# EIT_Recorder.net
KiCad netlist of a schematic drawn in EAGLE
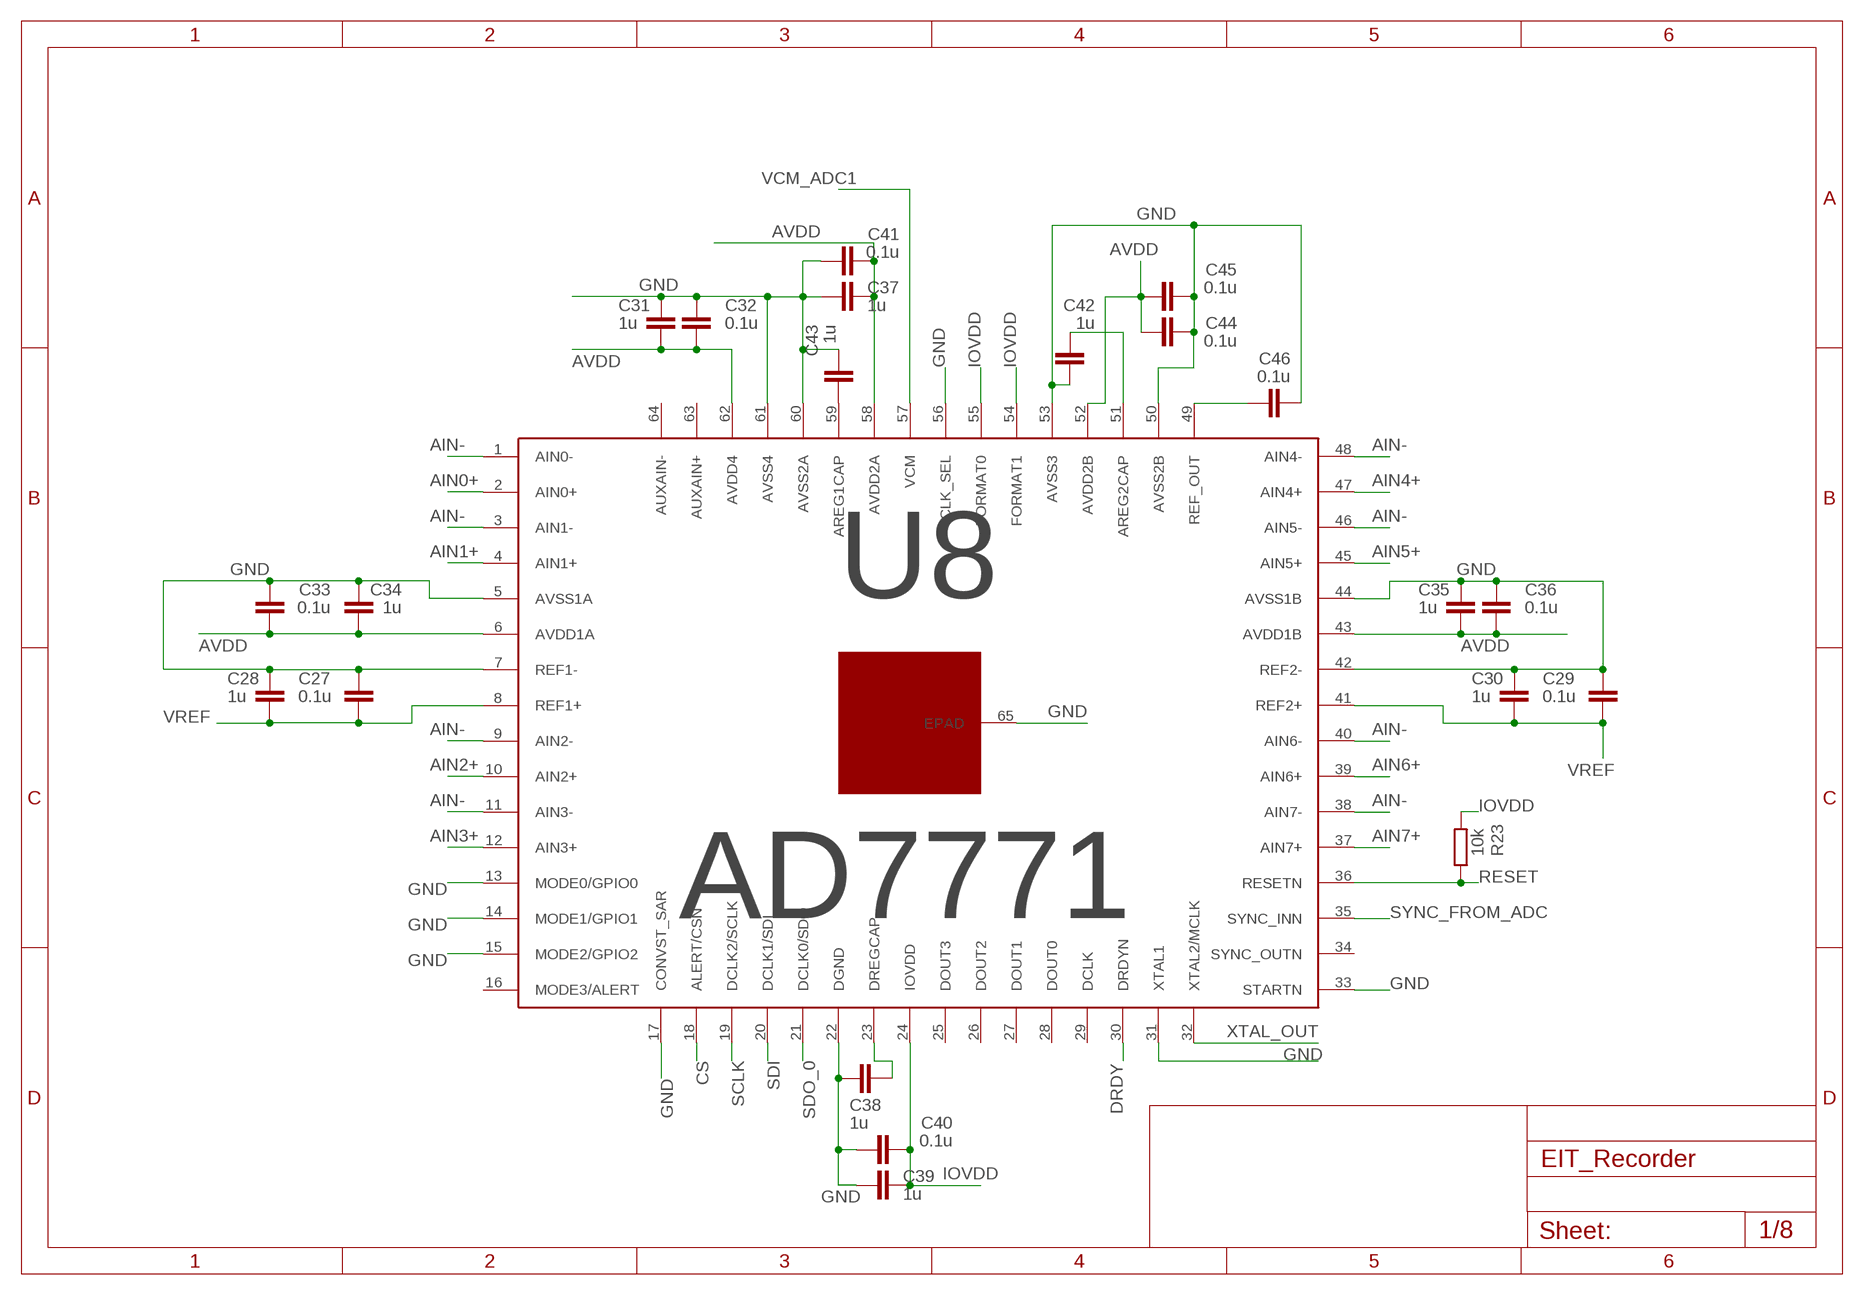
[diagram p0: schematic, sheet 1]
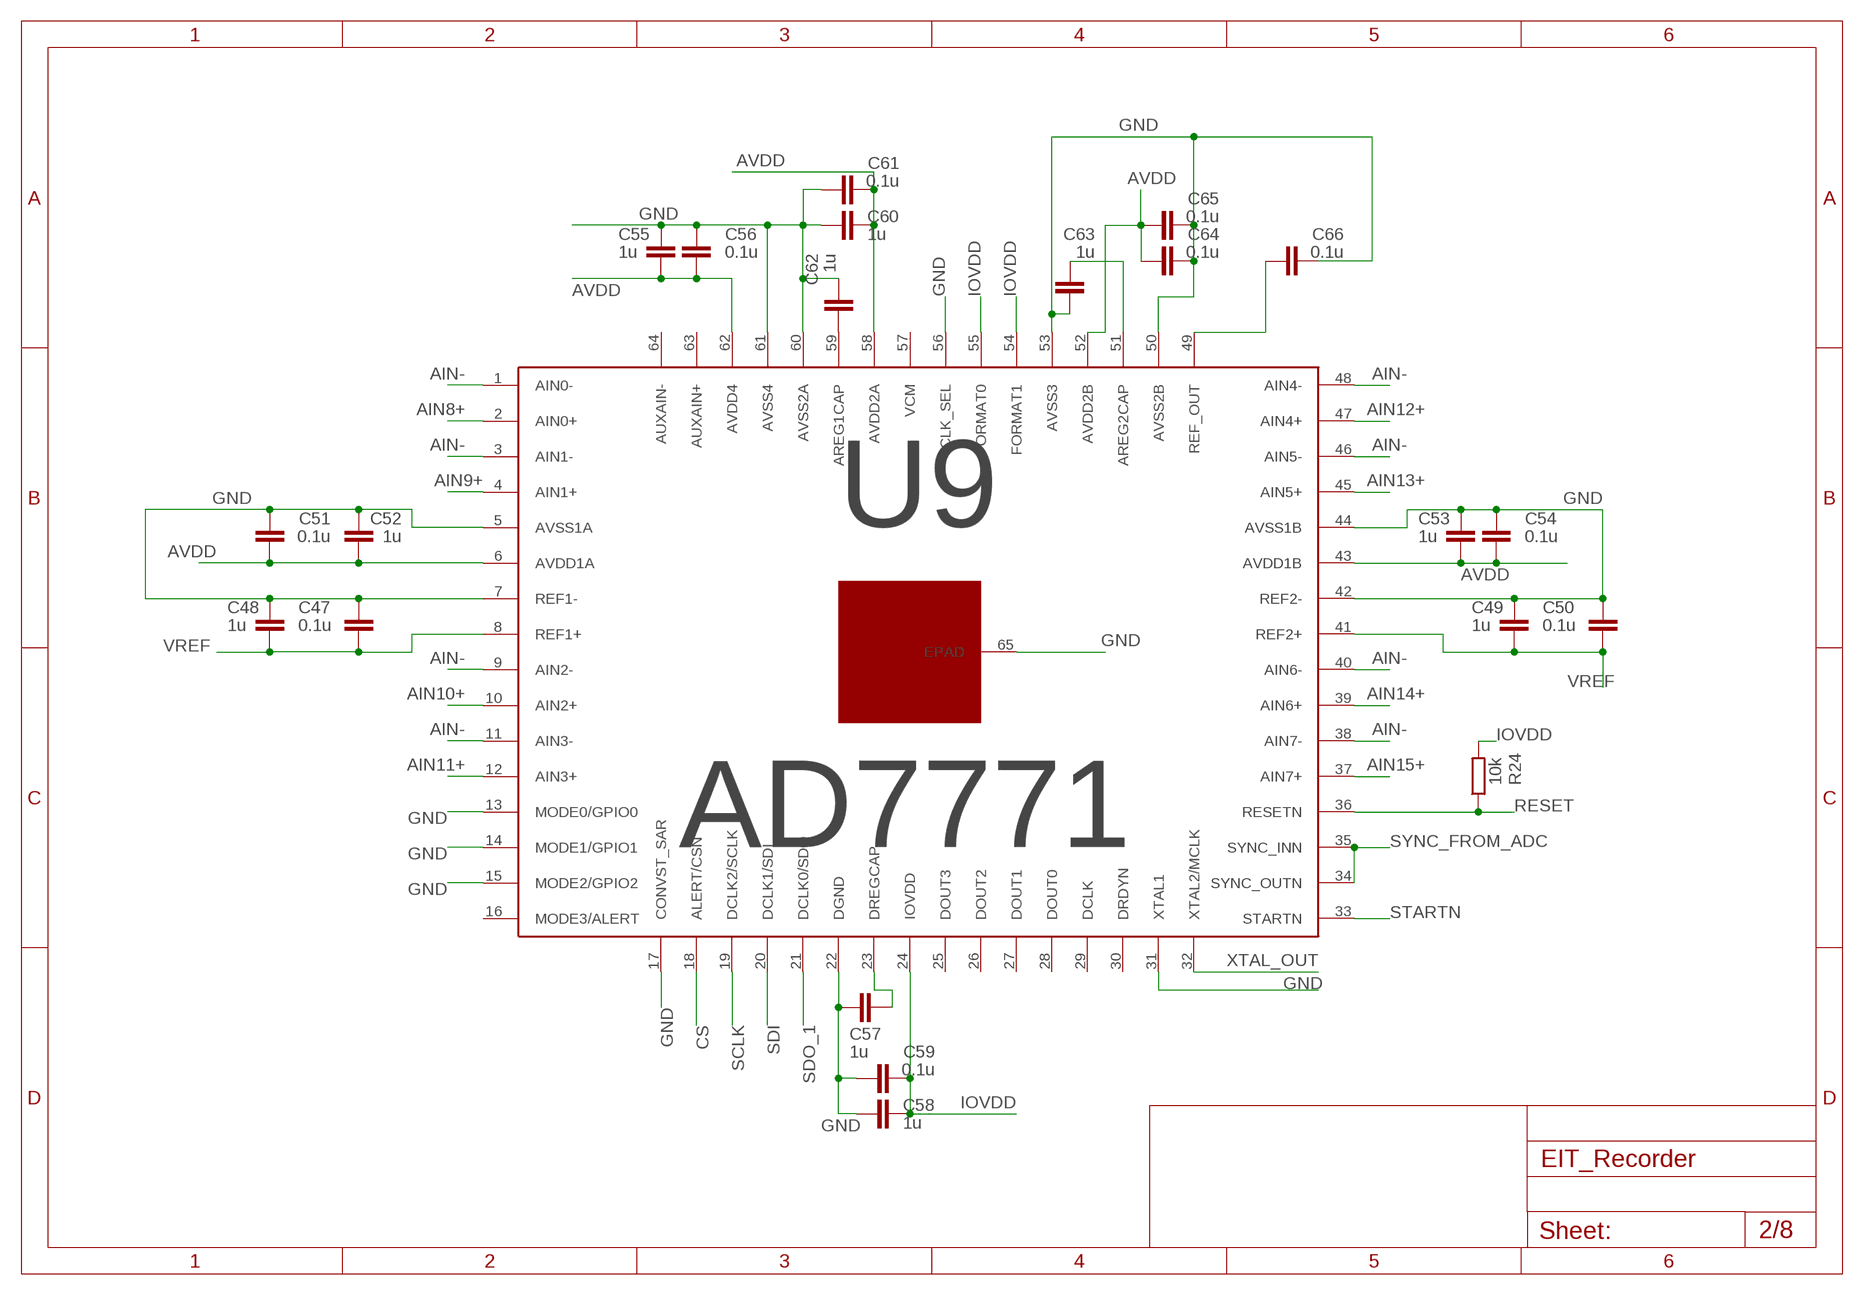
[diagram p1: schematic, sheet 2]
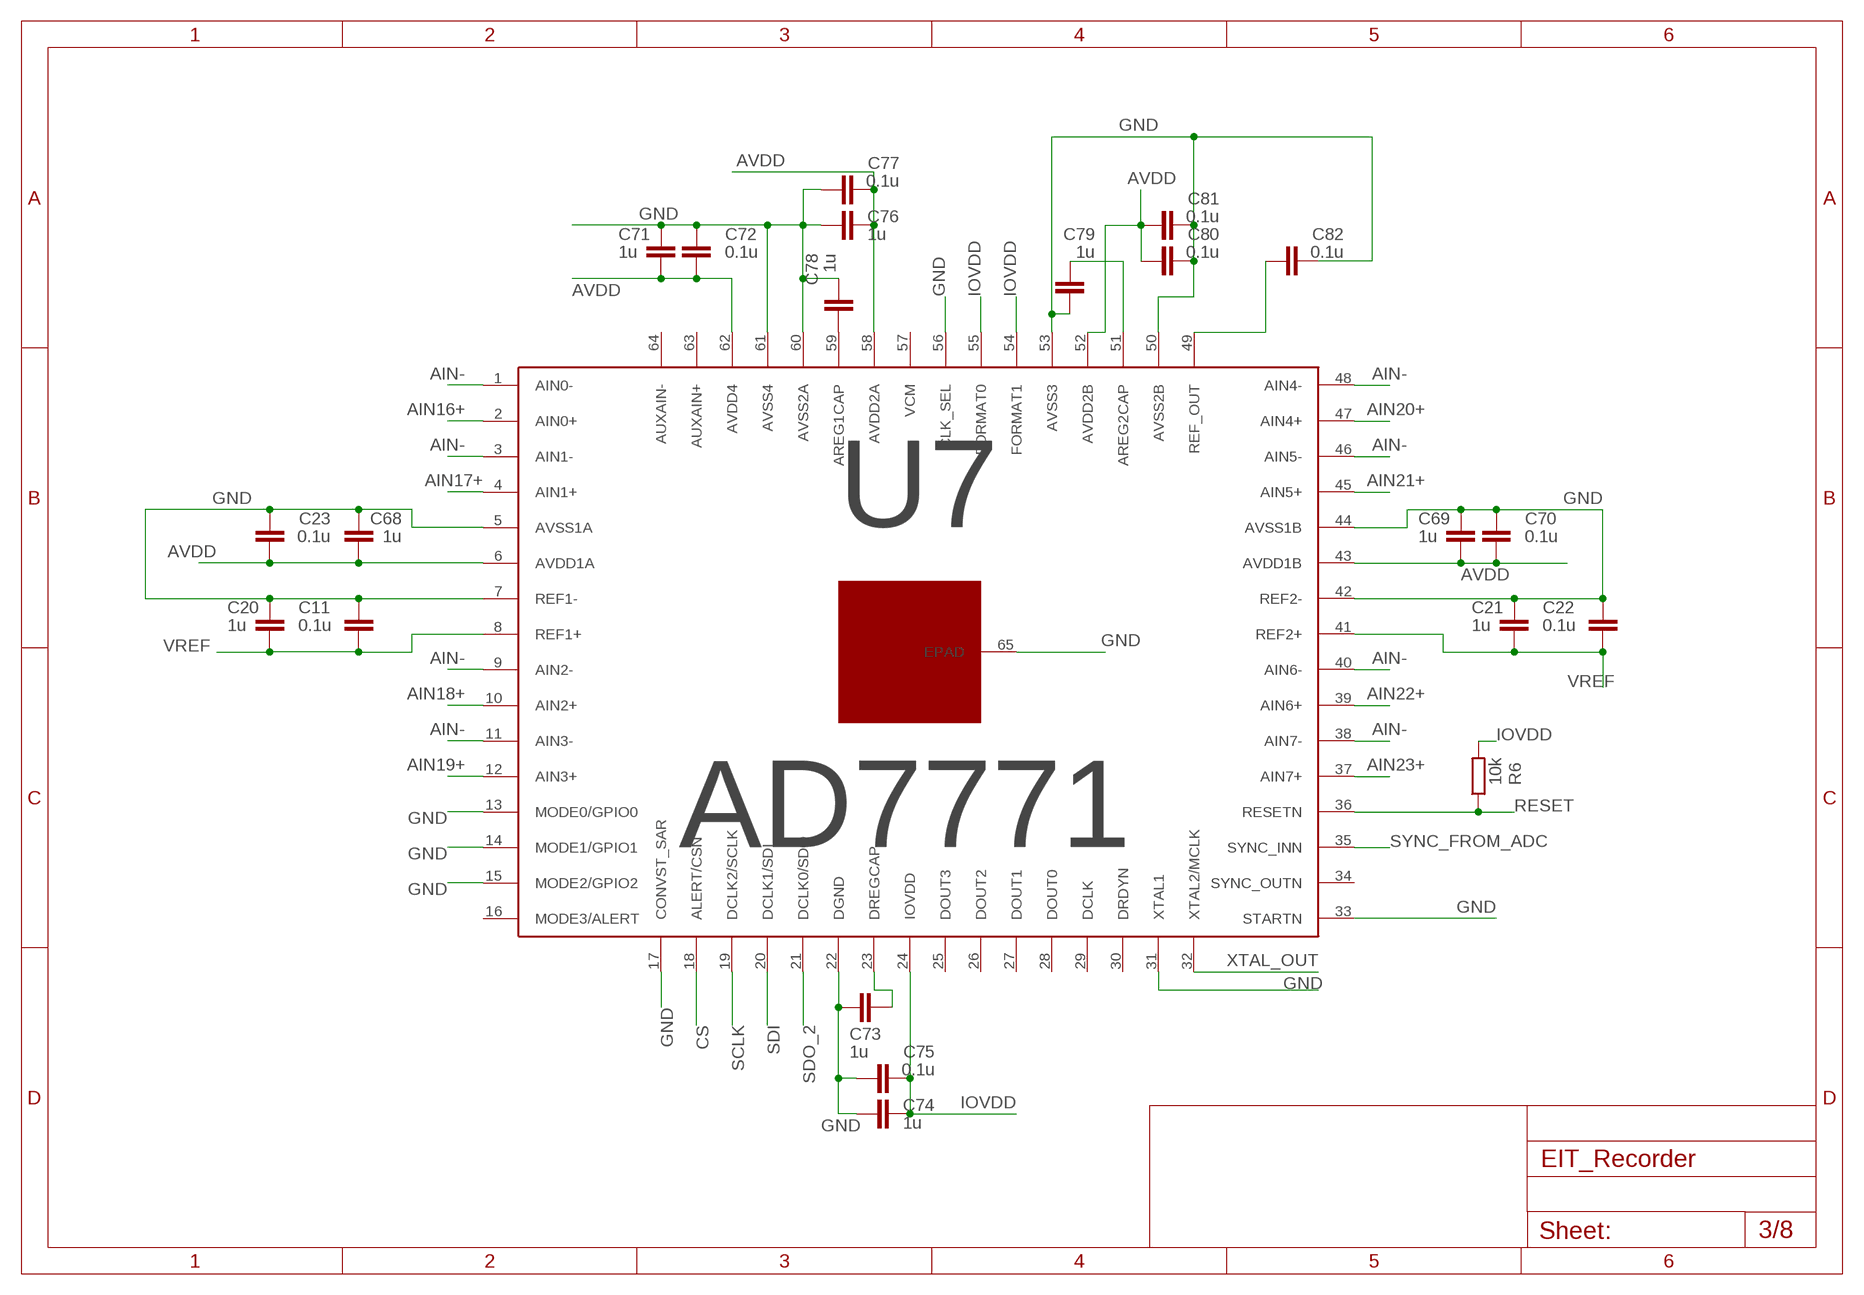
[diagram p2: schematic, sheet 3]
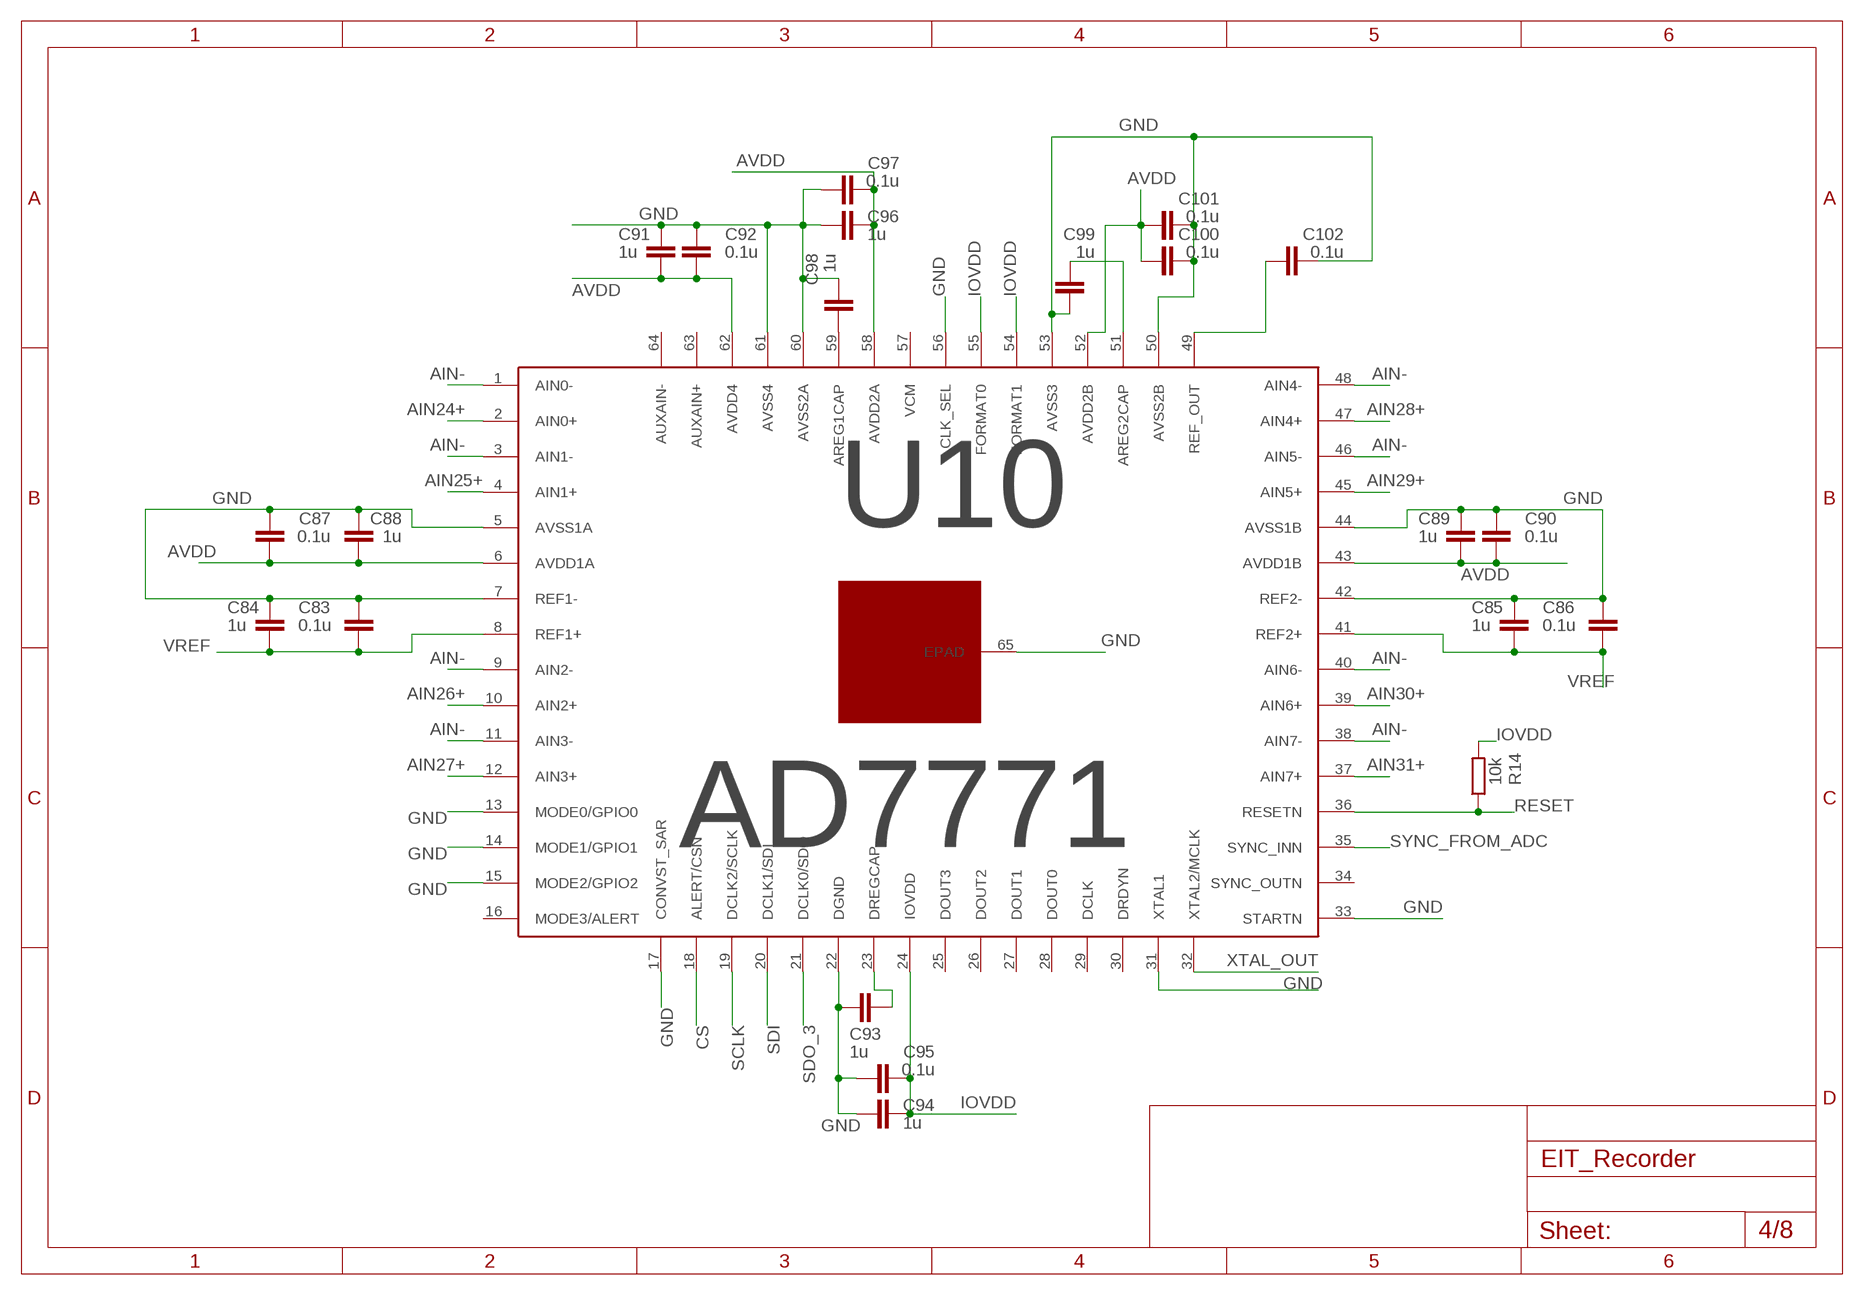
[diagram p3: schematic, sheet 4]
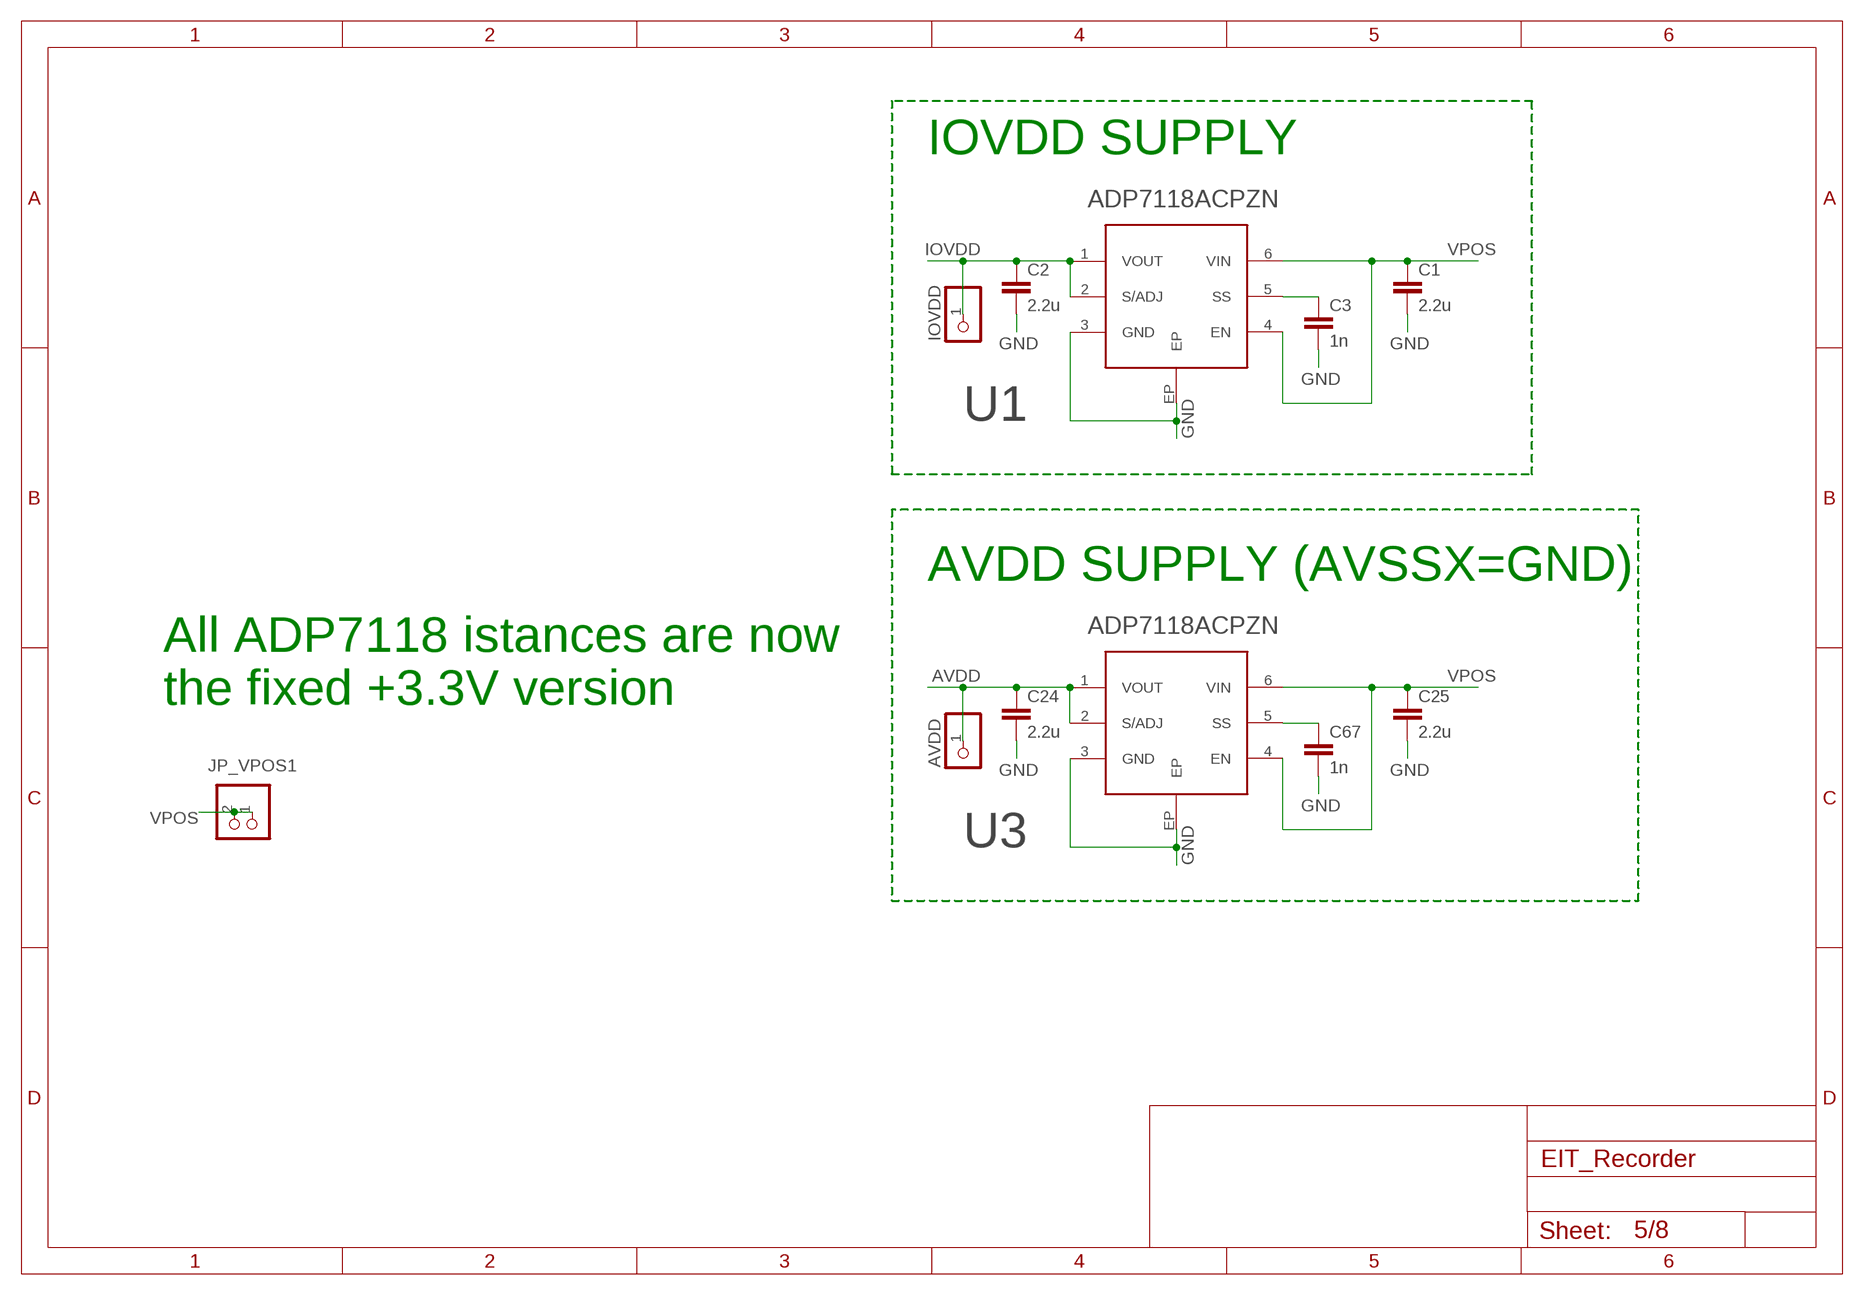
[diagram p4: schematic, sheet 5]
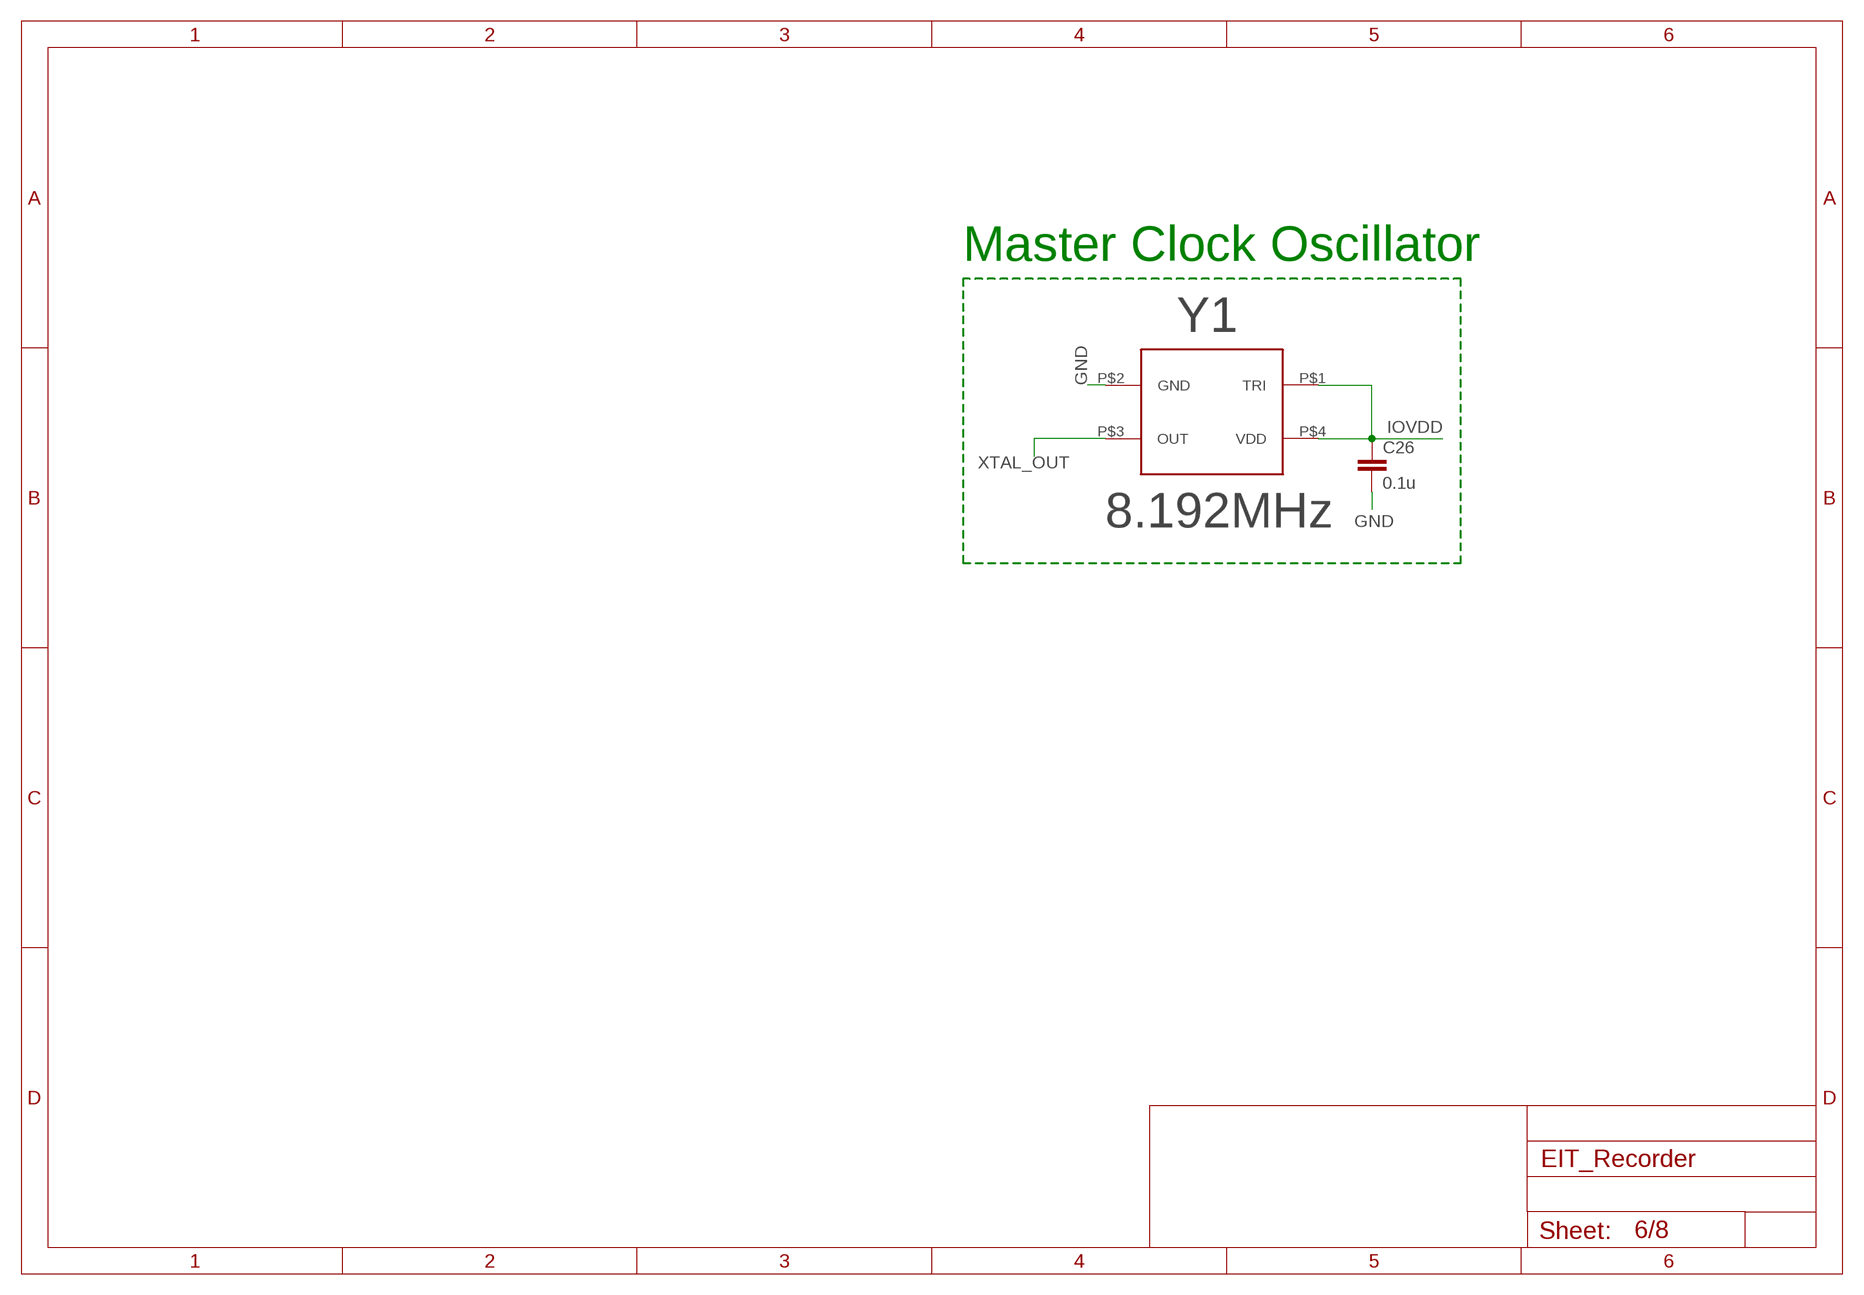
[diagram p5: schematic, sheet 6]
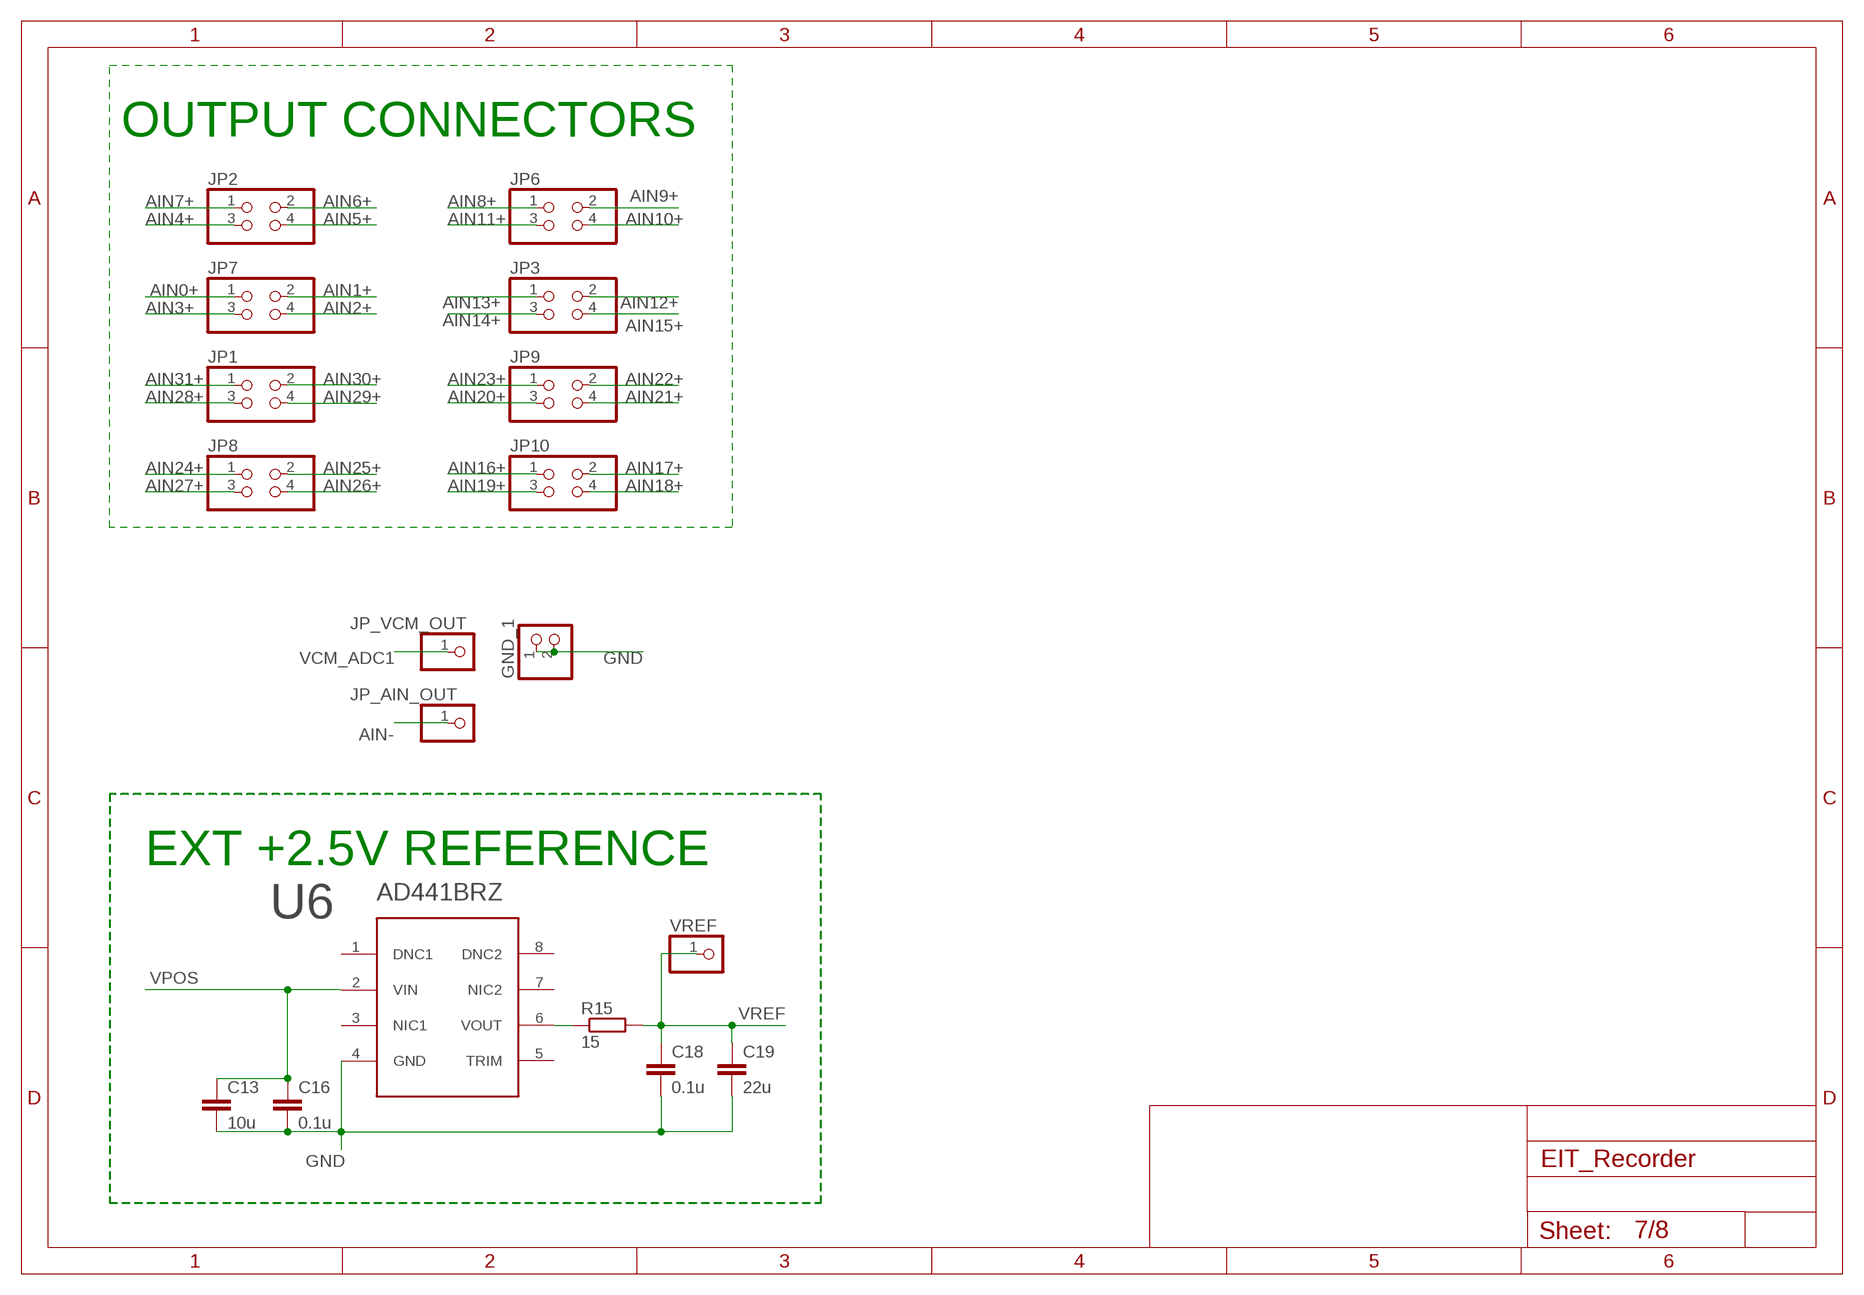
[diagram p6: schematic, sheet 7]
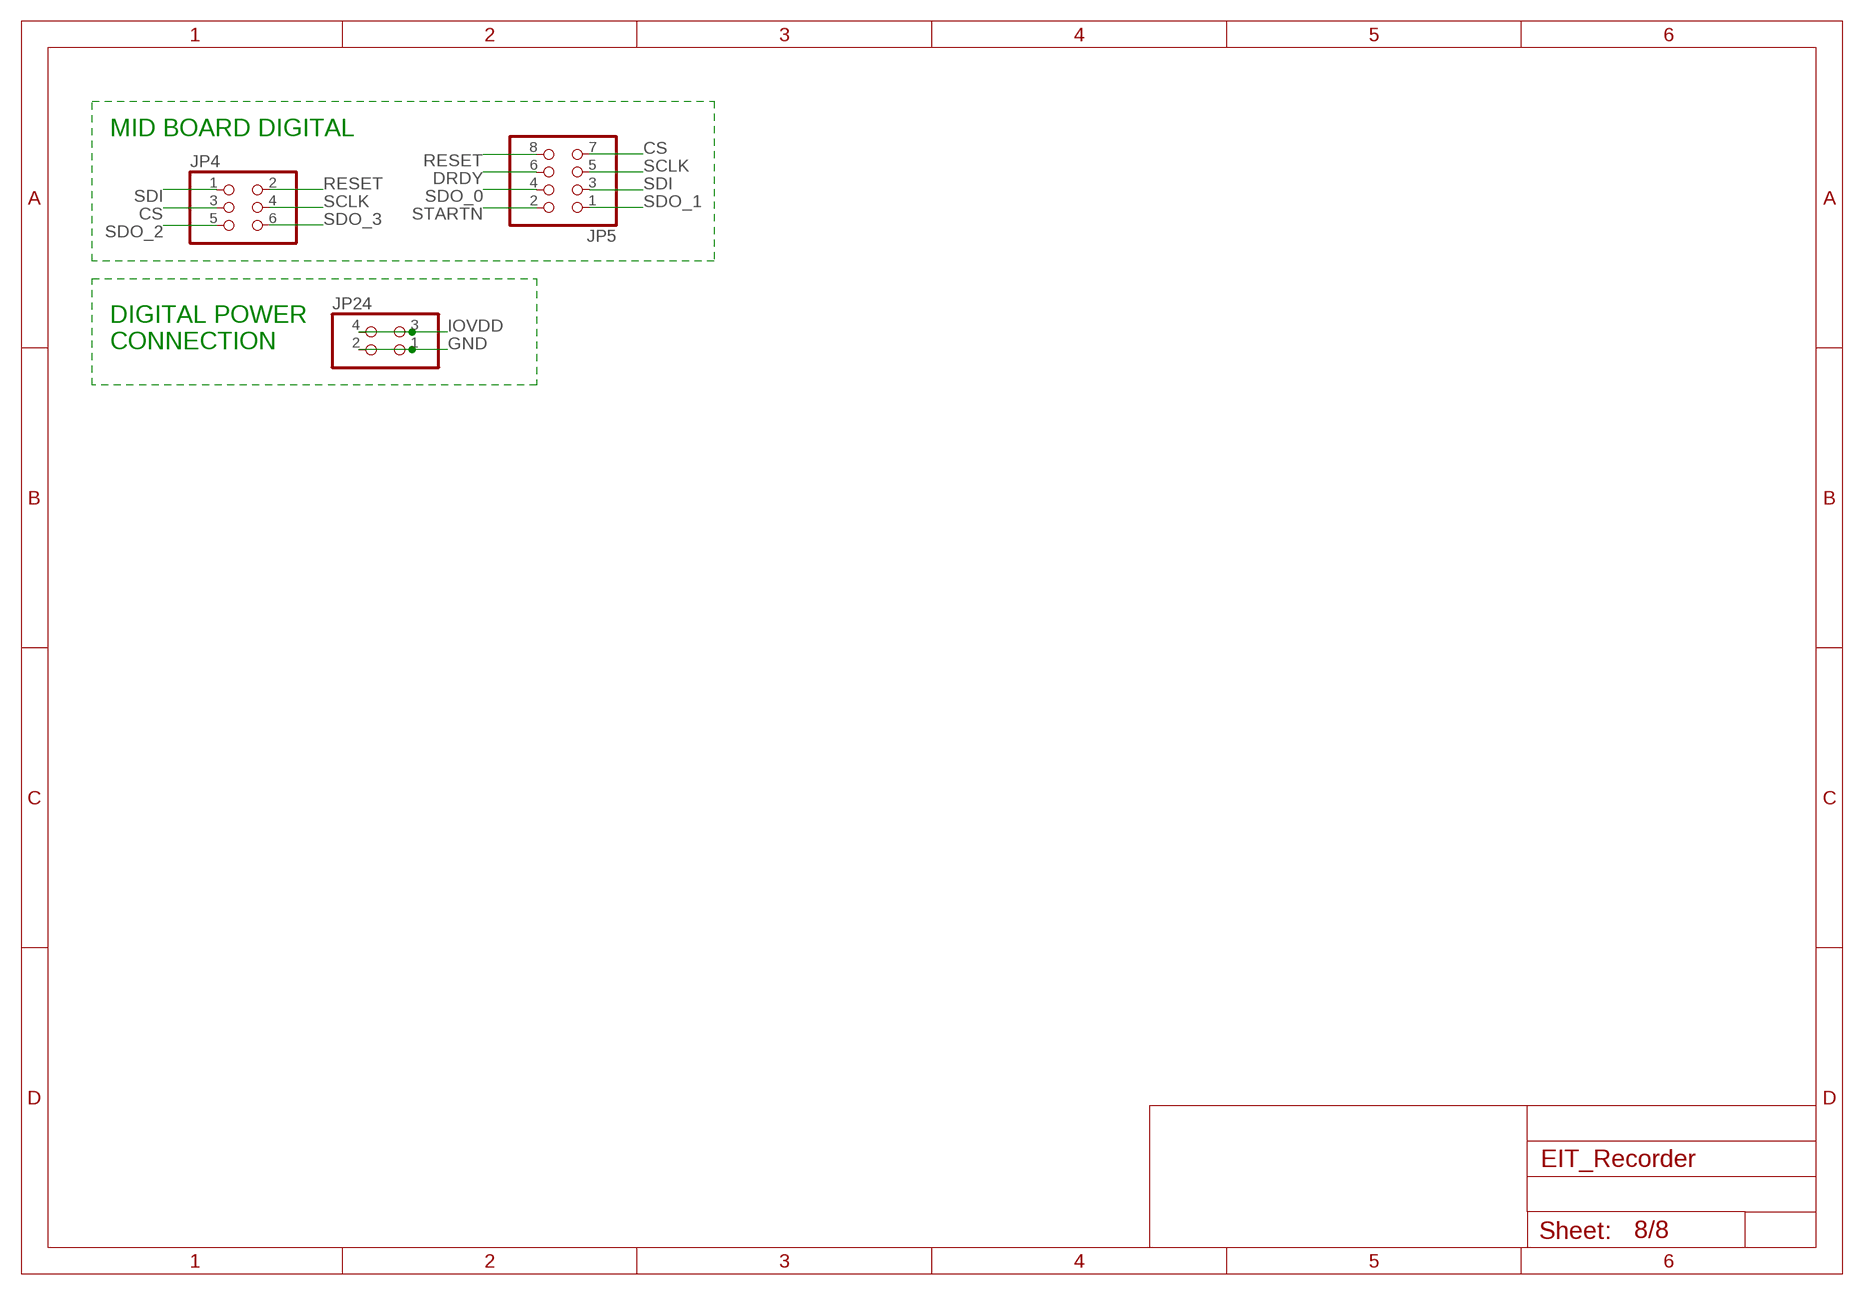
[diagram p7: schematic, sheet 8]

(export (version "E")
  (design (tool "Eeschema 10.0.6"))
  (components
    (comp (ref "C13")
      (value "10u")
      (footprint "eagle-import:C0805")
      (libsource (lib "eagle-import") (part "C0805"))
    )
    (comp (ref "C16")
      (value "0.1u")
      (footprint "eagle-import:C0402")
      (libsource (lib "eagle-import") (part "C0402"))
    )
    (comp (ref "C18")
      (value "0.1u")
      (footprint "eagle-import:C0402")
      (libsource (lib "eagle-import") (part "C0402"))
    )
    (comp (ref "C19")
      (value "22u")
      (footprint "eagle-import:C0805")
      (libsource (lib "eagle-import") (part "C0805"))
    )
    (comp (ref "GND_1")
      (value "PINHD-1X2")
      (footprint "eagle-import:1X02")
      (libsource (lib "eagle-import") (part "PINHD-1X2"))
    )
    (comp (ref "JP1")
      (value "PINHD-2X2")
      (footprint "eagle-import:2X02")
      (libsource (lib "eagle-import") (part "PINHD-2X2"))
    )
    (comp (ref "JP2")
      (value "PINHD-2X2")
      (footprint "eagle-import:2X02")
      (libsource (lib "eagle-import") (part "PINHD-2X2"))
    )
    (comp (ref "JP3")
      (value "PINHD-2X2")
      (footprint "eagle-import:2X02")
      (libsource (lib "eagle-import") (part "PINHD-2X2"))
    )
    (comp (ref "JP6")
      (value "PINHD-2X2")
      (footprint "eagle-import:2X02")
      (libsource (lib "eagle-import") (part "PINHD-2X2"))
    )
    (comp (ref "JP7")
      (value "PINHD-2X2")
      (footprint "eagle-import:2X02")
      (libsource (lib "eagle-import") (part "PINHD-2X2"))
    )
    (comp (ref "JP8")
      (value "PINHD-2X2")
      (footprint "eagle-import:2X02")
      (libsource (lib "eagle-import") (part "PINHD-2X2"))
    )
    (comp (ref "JP9")
      (value "PINHD-2X2")
      (footprint "eagle-import:2X02")
      (libsource (lib "eagle-import") (part "PINHD-2X2"))
    )
    (comp (ref "JP10")
      (value "PINHD-2X2")
      (footprint "eagle-import:2X02")
      (libsource (lib "eagle-import") (part "PINHD-2X2"))
    )
    (comp (ref "JP_AIN_OUT")
      (value "PINHD-1X1")
      (footprint "eagle-import:1X01")
      (libsource (lib "eagle-import") (part "PINHD-1X1"))
    )
    (comp (ref "JP_VCM_OUT")
      (value "PINHD-1X1")
      (footprint "eagle-import:1X01")
      (libsource (lib "eagle-import") (part "PINHD-1X1"))
    )
    (comp (ref "R15")
      (value "15")
      (footprint "eagle-import:R0603")
      (libsource (lib "eagle-import") (part "R0603"))
    )
    (comp (ref "U6")
      (value "AD441BRZ")
      (footprint "eagle-import:SOIC8N_CUSTOM")
      (libsource (lib "eagle-import") (part "AD441BRZ"))
    )
    (comp (ref "VREF")
      (value "PINHD-1X1")
      (footprint "eagle-import:1X01")
      (libsource (lib "eagle-import") (part "PINHD-1X1"))
    )
    (comp (ref "C47")
      (value "0.1u")
      (footprint "eagle-import:C0402")
      (libsource (lib "eagle-import") (part "C0402"))
    )
    (comp (ref "C48")
      (value "1u")
      (footprint "eagle-import:C0402")
      (libsource (lib "eagle-import") (part "C0402"))
    )
    (comp (ref "C49")
      (value "1u")
      (footprint "eagle-import:C0402")
      (libsource (lib "eagle-import") (part "C0402"))
    )
    (comp (ref "C50")
      (value "0.1u")
      (footprint "eagle-import:C0402")
      (libsource (lib "eagle-import") (part "C0402"))
    )
    (comp (ref "C51")
      (value "0.1u")
      (footprint "eagle-import:C0402")
      (libsource (lib "eagle-import") (part "C0402"))
    )
    (comp (ref "C52")
      (value "1u")
      (footprint "eagle-import:C0402")
      (libsource (lib "eagle-import") (part "C0402"))
    )
    (comp (ref "C53")
      (value "1u")
      (footprint "eagle-import:C0402")
      (libsource (lib "eagle-import") (part "C0402"))
    )
    (comp (ref "C54")
      (value "0.1u")
      (footprint "eagle-import:C0402")
      (libsource (lib "eagle-import") (part "C0402"))
    )
    (comp (ref "C55")
      (value "1u")
      (footprint "eagle-import:C0402")
      (libsource (lib "eagle-import") (part "C0402"))
    )
    (comp (ref "C56")
      (value "0.1u")
      (footprint "eagle-import:C0402")
      (libsource (lib "eagle-import") (part "C0402"))
    )
    (comp (ref "C57")
      (value "1u")
      (footprint "eagle-import:C0402")
      (libsource (lib "eagle-import") (part "C0402"))
    )
    (comp (ref "C58")
      (value "1u")
      (footprint "eagle-import:C0402")
      (libsource (lib "eagle-import") (part "C0402"))
    )
    (comp (ref "C59")
      (value "0.1u")
      (footprint "eagle-import:C0402")
      (libsource (lib "eagle-import") (part "C0402"))
    )
    (comp (ref "C60")
      (value "1u")
      (footprint "eagle-import:C0402")
      (libsource (lib "eagle-import") (part "C0402"))
    )
    (comp (ref "C61")
      (value "0.1u")
      (footprint "eagle-import:C0402")
      (libsource (lib "eagle-import") (part "C0402"))
    )
    (comp (ref "C62")
      (value "1u")
      (footprint "eagle-import:C0402")
      (libsource (lib "eagle-import") (part "C0402"))
    )
    (comp (ref "C63")
      (value "1u")
      (footprint "eagle-import:C0402")
      (libsource (lib "eagle-import") (part "C0402"))
    )
    (comp (ref "C64")
      (value "0.1u")
      (footprint "eagle-import:C0402")
      (libsource (lib "eagle-import") (part "C0402"))
    )
    (comp (ref "C65")
      (value "0.1u")
      (footprint "eagle-import:C0402")
      (libsource (lib "eagle-import") (part "C0402"))
    )
    (comp (ref "C66")
      (value "0.1u")
      (footprint "eagle-import:C0402")
      (libsource (lib "eagle-import") (part "C0402"))
    )
    (comp (ref "R24")
      (value "10k")
      (footprint "eagle-import:R0603")
      (libsource (lib "eagle-import") (part "R0603"))
    )
    (comp (ref "U9")
      (value "AD7771")
      (footprint "eagle-import:LFCSP64_CUSTOM")
      (libsource (lib "eagle-import") (part "AD7771"))
    )
    (comp (ref "AVDD")
      (value "PINHD-1X1")
      (footprint "eagle-import:1X01")
      (libsource (lib "eagle-import") (part "PINHD-1X1"))
    )
    (comp (ref "C1")
      (value "2.2u")
      (footprint "eagle-import:C0603")
      (libsource (lib "eagle-import") (part "C0603"))
    )
    (comp (ref "C2")
      (value "2.2u")
      (footprint "eagle-import:C0603")
      (libsource (lib "eagle-import") (part "C0603"))
    )
    (comp (ref "C3")
      (value "1n")
      (footprint "eagle-import:C0402")
      (libsource (lib "eagle-import") (part "C0402"))
    )
    (comp (ref "C24")
      (value "2.2u")
      (footprint "eagle-import:C0603")
      (libsource (lib "eagle-import") (part "C0603"))
    )
    (comp (ref "C25")
      (value "2.2u")
      (footprint "eagle-import:C0603")
      (libsource (lib "eagle-import") (part "C0603"))
    )
    (comp (ref "C67")
      (value "1n")
      (footprint "eagle-import:C0402")
      (libsource (lib "eagle-import") (part "C0402"))
    )
    (comp (ref "IOVDD")
      (value "PINHD-1X1")
      (footprint "eagle-import:1X01")
      (libsource (lib "eagle-import") (part "PINHD-1X1"))
    )
    (comp (ref "JP_VPOS1")
      (value "PINHD-1X2")
      (footprint "eagle-import:1X02")
      (libsource (lib "eagle-import") (part "PINHD-1X2"))
    )
    (comp (ref "U1")
      (value "ADP7118ACPZN")
      (footprint "eagle-import:LFCSP6_CUSTOM")
      (libsource (lib "eagle-import") (part "ADP7118ACPZN"))
    )
    (comp (ref "U3")
      (value "ADP7118ACPZN")
      (footprint "eagle-import:LFCSP6_CUSTOM")
      (libsource (lib "eagle-import") (part "ADP7118ACPZN"))
    )
    (comp (ref "C27")
      (value "0.1u")
      (footprint "eagle-import:C0402")
      (libsource (lib "eagle-import") (part "C0402"))
    )
    (comp (ref "C28")
      (value "1u")
      (footprint "eagle-import:C0402")
      (libsource (lib "eagle-import") (part "C0402"))
    )
    (comp (ref "C29")
      (value "0.1u")
      (footprint "eagle-import:C0402")
      (libsource (lib "eagle-import") (part "C0402"))
    )
    (comp (ref "C30")
      (value "1u")
      (footprint "eagle-import:C0402")
      (libsource (lib "eagle-import") (part "C0402"))
    )
    (comp (ref "C31")
      (value "1u")
      (footprint "eagle-import:C0402")
      (libsource (lib "eagle-import") (part "C0402"))
    )
    (comp (ref "C32")
      (value "0.1u")
      (footprint "eagle-import:C0402")
      (libsource (lib "eagle-import") (part "C0402"))
    )
    (comp (ref "C33")
      (value "0.1u")
      (footprint "eagle-import:C0402")
      (libsource (lib "eagle-import") (part "C0402"))
    )
    (comp (ref "C34")
      (value "1u")
      (footprint "eagle-import:C0402")
      (libsource (lib "eagle-import") (part "C0402"))
    )
    (comp (ref "C35")
      (value "1u")
      (footprint "eagle-import:C0402")
      (libsource (lib "eagle-import") (part "C0402"))
    )
    (comp (ref "C36")
      (value "0.1u")
      (footprint "eagle-import:C0402")
      (libsource (lib "eagle-import") (part "C0402"))
    )
    (comp (ref "C37")
      (value "1u")
      (footprint "eagle-import:C0402")
      (libsource (lib "eagle-import") (part "C0402"))
    )
    (comp (ref "C38")
      (value "1u")
      (footprint "eagle-import:C0402")
      (libsource (lib "eagle-import") (part "C0402"))
    )
    (comp (ref "C39")
      (value "1u")
      (footprint "eagle-import:C0402")
      (libsource (lib "eagle-import") (part "C0402"))
    )
    (comp (ref "C40")
      (value "0.1u")
      (footprint "eagle-import:C0402")
      (libsource (lib "eagle-import") (part "C0402"))
    )
    (comp (ref "C41")
      (value "0.1u")
      (footprint "eagle-import:C0402")
      (libsource (lib "eagle-import") (part "C0402"))
    )
    (comp (ref "C42")
      (value "1u")
      (footprint "eagle-import:C0402")
      (libsource (lib "eagle-import") (part "C0402"))
    )
    (comp (ref "C43")
      (value "1u")
      (footprint "eagle-import:C0402")
      (libsource (lib "eagle-import") (part "C0402"))
    )
    (comp (ref "C44")
      (value "0.1u")
      (footprint "eagle-import:C0402")
      (libsource (lib "eagle-import") (part "C0402"))
    )
    (comp (ref "C45")
      (value "0.1u")
      (footprint "eagle-import:C0402")
      (libsource (lib "eagle-import") (part "C0402"))
    )
    (comp (ref "C46")
      (value "0.1u")
      (footprint "eagle-import:C0402")
      (libsource (lib "eagle-import") (part "C0402"))
    )
    (comp (ref "R23")
      (value "10k")
      (footprint "eagle-import:R0603")
      (libsource (lib "eagle-import") (part "R0603"))
    )
    (comp (ref "U8")
      (value "AD7771")
      (footprint "eagle-import:LFCSP64_CUSTOM")
      (libsource (lib "eagle-import") (part "AD7771"))
    )
    (comp (ref "JP4")
      (value "PINHD-2X3")
      (footprint "eagle-import:2X03")
      (libsource (lib "eagle-import") (part "PINHD-2X3"))
    )
    (comp (ref "JP5")
      (value "PINHD-2X4")
      (footprint "eagle-import:2X04")
      (libsource (lib "eagle-import") (part "PINHD-2X4"))
    )
    (comp (ref "JP24")
      (value "PINHD-2X2")
      (footprint "eagle-import:2X02")
      (libsource (lib "eagle-import") (part "PINHD-2X2"))
    )
    (comp (ref "C83")
      (value "0.1u")
      (footprint "eagle-import:C0402")
      (libsource (lib "eagle-import") (part "C0402"))
    )
    (comp (ref "C84")
      (value "1u")
      (footprint "eagle-import:C0402")
      (libsource (lib "eagle-import") (part "C0402"))
    )
    (comp (ref "C85")
      (value "1u")
      (footprint "eagle-import:C0402")
      (libsource (lib "eagle-import") (part "C0402"))
    )
    (comp (ref "C86")
      (value "0.1u")
      (footprint "eagle-import:C0402")
      (libsource (lib "eagle-import") (part "C0402"))
    )
    (comp (ref "C87")
      (value "0.1u")
      (footprint "eagle-import:C0402")
      (libsource (lib "eagle-import") (part "C0402"))
    )
    (comp (ref "C88")
      (value "1u")
      (footprint "eagle-import:C0402")
      (libsource (lib "eagle-import") (part "C0402"))
    )
    (comp (ref "C89")
      (value "1u")
      (footprint "eagle-import:C0402")
      (libsource (lib "eagle-import") (part "C0402"))
    )
    (comp (ref "C90")
      (value "0.1u")
      (footprint "eagle-import:C0402")
      (libsource (lib "eagle-import") (part "C0402"))
    )
    (comp (ref "C91")
      (value "1u")
      (footprint "eagle-import:C0402")
      (libsource (lib "eagle-import") (part "C0402"))
    )
    (comp (ref "C92")
      (value "0.1u")
      (footprint "eagle-import:C0402")
      (libsource (lib "eagle-import") (part "C0402"))
    )
    (comp (ref "C93")
      (value "1u")
      (footprint "eagle-import:C0402")
      (libsource (lib "eagle-import") (part "C0402"))
    )
    (comp (ref "C94")
      (value "1u")
      (footprint "eagle-import:C0402")
      (libsource (lib "eagle-import") (part "C0402"))
    )
    (comp (ref "C95")
      (value "0.1u")
      (footprint "eagle-import:C0402")
      (libsource (lib "eagle-import") (part "C0402"))
    )
    (comp (ref "C96")
      (value "1u")
      (footprint "eagle-import:C0402")
      (libsource (lib "eagle-import") (part "C0402"))
    )
    (comp (ref "C97")
      (value "0.1u")
      (footprint "eagle-import:C0402")
      (libsource (lib "eagle-import") (part "C0402"))
    )
    (comp (ref "C98")
      (value "1u")
      (footprint "eagle-import:C0402")
      (libsource (lib "eagle-import") (part "C0402"))
    )
    (comp (ref "C99")
      (value "1u")
      (footprint "eagle-import:C0402")
      (libsource (lib "eagle-import") (part "C0402"))
    )
    (comp (ref "C100")
      (value "0.1u")
      (footprint "eagle-import:C0402")
      (libsource (lib "eagle-import") (part "C0402"))
    )
    (comp (ref "C101")
      (value "0.1u")
      (footprint "eagle-import:C0402")
      (libsource (lib "eagle-import") (part "C0402"))
    )
    (comp (ref "C102")
      (value "0.1u")
      (footprint "eagle-import:C0402")
      (libsource (lib "eagle-import") (part "C0402"))
    )
    (comp (ref "R14")
      (value "10k")
      (footprint "eagle-import:R0603")
      (libsource (lib "eagle-import") (part "R0603"))
    )
    (comp (ref "U10")
      (value "AD7771")
      (footprint "eagle-import:LFCSP64_CUSTOM")
      (libsource (lib "eagle-import") (part "AD7771"))
    )
    (comp (ref "C26")
      (value "0.1u")
      (footprint "eagle-import:C0402")
      (libsource (lib "eagle-import") (part "C0402"))
    )
    (comp (ref "Y1")
      (value "8.192MHz")
      (footprint "eagle-import:ECS-2520MVLC")
      (libsource (lib "eagle-import") (part "OSC-ECS-2520MVLC"))
    )
    (comp (ref "C11")
      (value "0.1u")
      (footprint "eagle-import:C0402")
      (libsource (lib "eagle-import") (part "C0402"))
    )
    (comp (ref "C20")
      (value "1u")
      (footprint "eagle-import:C0402")
      (libsource (lib "eagle-import") (part "C0402"))
    )
    (comp (ref "C21")
      (value "1u")
      (footprint "eagle-import:C0402")
      (libsource (lib "eagle-import") (part "C0402"))
    )
    (comp (ref "C22")
      (value "0.1u")
      (footprint "eagle-import:C0402")
      (libsource (lib "eagle-import") (part "C0402"))
    )
    (comp (ref "C23")
      (value "0.1u")
      (footprint "eagle-import:C0402")
      (libsource (lib "eagle-import") (part "C0402"))
    )
    (comp (ref "C68")
      (value "1u")
      (footprint "eagle-import:C0402")
      (libsource (lib "eagle-import") (part "C0402"))
    )
    (comp (ref "C69")
      (value "1u")
      (footprint "eagle-import:C0402")
      (libsource (lib "eagle-import") (part "C0402"))
    )
    (comp (ref "C70")
      (value "0.1u")
      (footprint "eagle-import:C0402")
      (libsource (lib "eagle-import") (part "C0402"))
    )
    (comp (ref "C71")
      (value "1u")
      (footprint "eagle-import:C0402")
      (libsource (lib "eagle-import") (part "C0402"))
    )
    (comp (ref "C72")
      (value "0.1u")
      (footprint "eagle-import:C0402")
      (libsource (lib "eagle-import") (part "C0402"))
    )
    (comp (ref "C73")
      (value "1u")
      (footprint "eagle-import:C0402")
      (libsource (lib "eagle-import") (part "C0402"))
    )
    (comp (ref "C74")
      (value "1u")
      (footprint "eagle-import:C0402")
      (libsource (lib "eagle-import") (part "C0402"))
    )
    (comp (ref "C75")
      (value "0.1u")
      (footprint "eagle-import:C0402")
      (libsource (lib "eagle-import") (part "C0402"))
    )
    (comp (ref "C76")
      (value "1u")
      (footprint "eagle-import:C0402")
      (libsource (lib "eagle-import") (part "C0402"))
    )
    (comp (ref "C77")
      (value "0.1u")
      (footprint "eagle-import:C0402")
      (libsource (lib "eagle-import") (part "C0402"))
    )
    (comp (ref "C78")
      (value "1u")
      (footprint "eagle-import:C0402")
      (libsource (lib "eagle-import") (part "C0402"))
    )
    (comp (ref "C79")
      (value "1u")
      (footprint "eagle-import:C0402")
      (libsource (lib "eagle-import") (part "C0402"))
    )
    (comp (ref "C80")
      (value "0.1u")
      (footprint "eagle-import:C0402")
      (libsource (lib "eagle-import") (part "C0402"))
    )
    (comp (ref "C81")
      (value "0.1u")
      (footprint "eagle-import:C0402")
      (libsource (lib "eagle-import") (part "C0402"))
    )
    (comp (ref "C82")
      (value "0.1u")
      (footprint "eagle-import:C0402")
      (libsource (lib "eagle-import") (part "C0402"))
    )
    (comp (ref "R6")
      (value "10k")
      (footprint "eagle-import:R0603")
      (libsource (lib "eagle-import") (part "R0603"))
    )
    (comp (ref "U7")
      (value "AD7771")
      (footprint "eagle-import:LFCSP64_CUSTOM")
      (libsource (lib "eagle-import") (part "AD7771"))
    )
  )
  (nets
    (net (code "1") (name "AIN-") (class "Default")
      (node (ref "JP_AIN_OUT") (pin "1") (pinfunction "1_1") (pintype "passive"))
      (node (ref "U10") (pin "1") (pinfunction "AIN0-_1") (pintype "bidirectional"))
      (node (ref "U10") (pin "11") (pinfunction "AIN3-_11") (pintype "bidirectional"))
      (node (ref "U10") (pin "3") (pinfunction "AIN1-_3") (pintype "bidirectional"))
      (node (ref "U10") (pin "38") (pinfunction "AIN7-_38") (pintype "input"))
      (node (ref "U10") (pin "40") (pinfunction "AIN6-_40") (pintype "input"))
      (node (ref "U10") (pin "46") (pinfunction "AIN5-_46") (pintype "input"))
      (node (ref "U10") (pin "48") (pinfunction "AIN4-_48") (pintype "input"))
      (node (ref "U10") (pin "9") (pinfunction "AIN2-_9") (pintype "bidirectional"))
      (node (ref "U7") (pin "1") (pinfunction "AIN0-_1") (pintype "bidirectional"))
      (node (ref "U7") (pin "11") (pinfunction "AIN3-_11") (pintype "bidirectional"))
      (node (ref "U7") (pin "3") (pinfunction "AIN1-_3") (pintype "bidirectional"))
      (node (ref "U7") (pin "38") (pinfunction "AIN7-_38") (pintype "input"))
      (node (ref "U7") (pin "40") (pinfunction "AIN6-_40") (pintype "input"))
      (node (ref "U7") (pin "46") (pinfunction "AIN5-_46") (pintype "input"))
      (node (ref "U7") (pin "48") (pinfunction "AIN4-_48") (pintype "input"))
      (node (ref "U7") (pin "9") (pinfunction "AIN2-_9") (pintype "bidirectional"))
      (node (ref "U8") (pin "1") (pinfunction "AIN0-_1") (pintype "bidirectional"))
      (node (ref "U8") (pin "11") (pinfunction "AIN3-_11") (pintype "bidirectional"))
      (node (ref "U8") (pin "3") (pinfunction "AIN1-_3") (pintype "bidirectional"))
      (node (ref "U8") (pin "38") (pinfunction "AIN7-_38") (pintype "input"))
      (node (ref "U8") (pin "40") (pinfunction "AIN6-_40") (pintype "input"))
      (node (ref "U8") (pin "46") (pinfunction "AIN5-_46") (pintype "input"))
      (node (ref "U8") (pin "48") (pinfunction "AIN4-_48") (pintype "input"))
      (node (ref "U8") (pin "9") (pinfunction "AIN2-_9") (pintype "bidirectional"))
      (node (ref "U9") (pin "1") (pinfunction "AIN0-_1") (pintype "bidirectional"))
      (node (ref "U9") (pin "11") (pinfunction "AIN3-_11") (pintype "bidirectional"))
      (node (ref "U9") (pin "3") (pinfunction "AIN1-_3") (pintype "bidirectional"))
      (node (ref "U9") (pin "38") (pinfunction "AIN7-_38") (pintype "input"))
      (node (ref "U9") (pin "40") (pinfunction "AIN6-_40") (pintype "input"))
      (node (ref "U9") (pin "46") (pinfunction "AIN5-_46") (pintype "input"))
      (node (ref "U9") (pin "48") (pinfunction "AIN4-_48") (pintype "input"))
      (node (ref "U9") (pin "9") (pinfunction "AIN2-_9") (pintype "bidirectional"))
    )
    (net (code "2") (name "AIN0+") (class "Default")
      (node (ref "JP7") (pin "1") (pinfunction "1_1") (pintype "passive"))
      (node (ref "U8") (pin "2") (pinfunction "AIN0+_2") (pintype "bidirectional"))
    )
    (net (code "3") (name "AIN1+") (class "Default")
      (node (ref "JP7") (pin "2") (pinfunction "2_2") (pintype "passive"))
      (node (ref "U8") (pin "4") (pinfunction "AIN1+_4") (pintype "input"))
    )
    (net (code "4") (name "AIN2+") (class "Default")
      (node (ref "JP7") (pin "4") (pinfunction "4_4") (pintype "passive"))
      (node (ref "U8") (pin "10") (pinfunction "AIN2+_10") (pintype "bidirectional"))
    )
    (net (code "5") (name "AIN3+") (class "Default")
      (node (ref "JP7") (pin "3") (pinfunction "3_3") (pintype "passive"))
      (node (ref "U8") (pin "12") (pinfunction "AIN3+_12") (pintype "input"))
    )
    (net (code "6") (name "AIN4+") (class "Default")
      (node (ref "JP2") (pin "3") (pinfunction "3_3") (pintype "passive"))
      (node (ref "U8") (pin "47") (pinfunction "AIN4+_47") (pintype "input"))
    )
    (net (code "7") (name "AIN5+") (class "Default")
      (node (ref "JP2") (pin "4") (pinfunction "4_4") (pintype "passive"))
      (node (ref "U8") (pin "45") (pinfunction "AIN5+_45") (pintype "input"))
    )
    (net (code "8") (name "AIN6+") (class "Default")
      (node (ref "JP2") (pin "2") (pinfunction "2_2") (pintype "passive"))
      (node (ref "U8") (pin "39") (pinfunction "AIN6+_39") (pintype "input"))
    )
    (net (code "9") (name "AIN7+") (class "Default")
      (node (ref "JP2") (pin "1") (pinfunction "1_1") (pintype "passive"))
      (node (ref "U8") (pin "37") (pinfunction "AIN7+_37") (pintype "input"))
    )
    (net (code "10") (name "AIN8+") (class "Default")
      (node (ref "JP6") (pin "1") (pinfunction "1_1") (pintype "passive"))
      (node (ref "U9") (pin "2") (pinfunction "AIN0+_2") (pintype "bidirectional"))
    )
    (net (code "11") (name "AIN9+") (class "Default")
      (node (ref "JP6") (pin "2") (pinfunction "2_2") (pintype "passive"))
      (node (ref "U9") (pin "4") (pinfunction "AIN1+_4") (pintype "input"))
    )
    (net (code "12") (name "AIN10+") (class "Default")
      (node (ref "JP6") (pin "4") (pinfunction "4_4") (pintype "passive"))
      (node (ref "U9") (pin "10") (pinfunction "AIN2+_10") (pintype "bidirectional"))
    )
    (net (code "13") (name "AIN11+") (class "Default")
      (node (ref "JP6") (pin "3") (pinfunction "3_3") (pintype "passive"))
      (node (ref "U9") (pin "12") (pinfunction "AIN3+_12") (pintype "input"))
    )
    (net (code "14") (name "AIN12+") (class "Default")
      (node (ref "JP3") (pin "2") (pinfunction "2_2") (pintype "passive"))
      (node (ref "U9") (pin "47") (pinfunction "AIN4+_47") (pintype "input"))
    )
    (net (code "15") (name "AIN13+") (class "Default")
      (node (ref "JP3") (pin "1") (pinfunction "1_1") (pintype "passive"))
      (node (ref "U9") (pin "45") (pinfunction "AIN5+_45") (pintype "input"))
    )
    (net (code "16") (name "AIN14+") (class "Default")
      (node (ref "JP3") (pin "3") (pinfunction "3_3") (pintype "passive"))
      (node (ref "U9") (pin "39") (pinfunction "AIN6+_39") (pintype "input"))
    )
    (net (code "17") (name "AIN15+") (class "Default")
      (node (ref "JP3") (pin "4") (pinfunction "4_4") (pintype "passive"))
      (node (ref "U9") (pin "37") (pinfunction "AIN7+_37") (pintype "input"))
    )
    (net (code "18") (name "AIN16+") (class "Default")
      (node (ref "JP10") (pin "1") (pinfunction "1_1") (pintype "passive"))
      (node (ref "U7") (pin "2") (pinfunction "AIN0+_2") (pintype "bidirectional"))
    )
    (net (code "19") (name "AIN17+") (class "Default")
      (node (ref "JP10") (pin "2") (pinfunction "2_2") (pintype "passive"))
      (node (ref "U7") (pin "4") (pinfunction "AIN1+_4") (pintype "input"))
    )
    (net (code "20") (name "AIN18+") (class "Default")
      (node (ref "JP10") (pin "4") (pinfunction "4_4") (pintype "passive"))
      (node (ref "U7") (pin "10") (pinfunction "AIN2+_10") (pintype "bidirectional"))
    )
    (net (code "21") (name "AIN19+") (class "Default")
      (node (ref "JP10") (pin "3") (pinfunction "3_3") (pintype "passive"))
      (node (ref "U7") (pin "12") (pinfunction "AIN3+_12") (pintype "input"))
    )
    (net (code "22") (name "AIN20+") (class "Default")
      (node (ref "JP9") (pin "3") (pinfunction "3_3") (pintype "passive"))
      (node (ref "U7") (pin "47") (pinfunction "AIN4+_47") (pintype "input"))
    )
    (net (code "23") (name "AIN21+") (class "Default")
      (node (ref "JP9") (pin "4") (pinfunction "4_4") (pintype "passive"))
      (node (ref "U7") (pin "45") (pinfunction "AIN5+_45") (pintype "input"))
    )
    (net (code "24") (name "AIN22+") (class "Default")
      (node (ref "JP9") (pin "2") (pinfunction "2_2") (pintype "passive"))
      (node (ref "U7") (pin "39") (pinfunction "AIN6+_39") (pintype "input"))
    )
    (net (code "25") (name "AIN23+") (class "Default")
      (node (ref "JP9") (pin "1") (pinfunction "1_1") (pintype "passive"))
      (node (ref "U7") (pin "37") (pinfunction "AIN7+_37") (pintype "input"))
    )
    (net (code "26") (name "AIN24+") (class "Default")
      (node (ref "JP8") (pin "1") (pinfunction "1_1") (pintype "passive"))
      (node (ref "U10") (pin "2") (pinfunction "AIN0+_2") (pintype "bidirectional"))
    )
    (net (code "27") (name "AIN25+") (class "Default")
      (node (ref "JP8") (pin "2") (pinfunction "2_2") (pintype "passive"))
      (node (ref "U10") (pin "4") (pinfunction "AIN1+_4") (pintype "input"))
    )
    (net (code "28") (name "AIN26+") (class "Default")
      (node (ref "JP8") (pin "4") (pinfunction "4_4") (pintype "passive"))
      (node (ref "U10") (pin "10") (pinfunction "AIN2+_10") (pintype "bidirectional"))
    )
    (net (code "29") (name "AIN27+") (class "Default")
      (node (ref "JP8") (pin "3") (pinfunction "3_3") (pintype "passive"))
      (node (ref "U10") (pin "12") (pinfunction "AIN3+_12") (pintype "input"))
    )
    (net (code "30") (name "AIN28+") (class "Default")
      (node (ref "JP1") (pin "3") (pinfunction "3_3") (pintype "passive"))
      (node (ref "U10") (pin "47") (pinfunction "AIN4+_47") (pintype "input"))
    )
    (net (code "31") (name "AIN29+") (class "Default")
      (node (ref "JP1") (pin "4") (pinfunction "4_4") (pintype "passive"))
      (node (ref "U10") (pin "45") (pinfunction "AIN5+_45") (pintype "input"))
    )
    (net (code "32") (name "AIN30+") (class "Default")
      (node (ref "JP1") (pin "2") (pinfunction "2_2") (pintype "passive"))
      (node (ref "U10") (pin "39") (pinfunction "AIN6+_39") (pintype "input"))
    )
    (net (code "33") (name "AIN31+") (class "Default")
      (node (ref "JP1") (pin "1") (pinfunction "1_1") (pintype "passive"))
      (node (ref "U10") (pin "37") (pinfunction "AIN7+_37") (pintype "input"))
    )
    (net (code "34") (name "AVDD") (class "Default")
      (node (ref "AVDD") (pin "1") (pinfunction "1_1") (pintype "passive"))
      (node (ref "C100") (pin "2") (pinfunction "2_2") (pintype "passive"))
      (node (ref "C101") (pin "2") (pinfunction "2_2") (pintype "passive"))
      (node (ref "C23") (pin "1") (pinfunction "1_1") (pintype "passive"))
      (node (ref "C24") (pin "1") (pinfunction "1_1") (pintype "passive"))
      (node (ref "C31") (pin "1") (pinfunction "1_1") (pintype "passive"))
      (node (ref "C32") (pin "1") (pinfunction "1_1") (pintype "passive"))
      (node (ref "C33") (pin "1") (pinfunction "1_1") (pintype "passive"))
      (node (ref "C34") (pin "1") (pinfunction "1_1") (pintype "passive"))
      (node (ref "C35") (pin "1") (pinfunction "1_1") (pintype "passive"))
      (node (ref "C36") (pin "1") (pinfunction "1_1") (pintype "passive"))
      (node (ref "C37") (pin "1") (pinfunction "1_1") (pintype "passive"))
      (node (ref "C41") (pin "1") (pinfunction "1_1") (pintype "passive"))
      (node (ref "C44") (pin "2") (pinfunction "2_2") (pintype "passive"))
      (node (ref "C45") (pin "2") (pinfunction "2_2") (pintype "passive"))
      (node (ref "C51") (pin "1") (pinfunction "1_1") (pintype "passive"))
      (node (ref "C52") (pin "1") (pinfunction "1_1") (pintype "passive"))
      (node (ref "C53") (pin "1") (pinfunction "1_1") (pintype "passive"))
      (node (ref "C54") (pin "1") (pinfunction "1_1") (pintype "passive"))
      (node (ref "C55") (pin "1") (pinfunction "1_1") (pintype "passive"))
      (node (ref "C56") (pin "1") (pinfunction "1_1") (pintype "passive"))
      (node (ref "C60") (pin "1") (pinfunction "1_1") (pintype "passive"))
      (node (ref "C61") (pin "1") (pinfunction "1_1") (pintype "passive"))
      (node (ref "C64") (pin "2") (pinfunction "2_2") (pintype "passive"))
      (node (ref "C65") (pin "2") (pinfunction "2_2") (pintype "passive"))
      (node (ref "C68") (pin "1") (pinfunction "1_1") (pintype "passive"))
      (node (ref "C69") (pin "1") (pinfunction "1_1") (pintype "passive"))
      (node (ref "C70") (pin "1") (pinfunction "1_1") (pintype "passive"))
      (node (ref "C71") (pin "1") (pinfunction "1_1") (pintype "passive"))
      (node (ref "C72") (pin "1") (pinfunction "1_1") (pintype "passive"))
      (node (ref "C76") (pin "1") (pinfunction "1_1") (pintype "passive"))
      (node (ref "C77") (pin "1") (pinfunction "1_1") (pintype "passive"))
      (node (ref "C80") (pin "2") (pinfunction "2_2") (pintype "passive"))
      (node (ref "C81") (pin "2") (pinfunction "2_2") (pintype "passive"))
      (node (ref "C87") (pin "1") (pinfunction "1_1") (pintype "passive"))
      (node (ref "C88") (pin "1") (pinfunction "1_1") (pintype "passive"))
      (node (ref "C89") (pin "1") (pinfunction "1_1") (pintype "passive"))
      (node (ref "C90") (pin "1") (pinfunction "1_1") (pintype "passive"))
      (node (ref "C91") (pin "1") (pinfunction "1_1") (pintype "passive"))
      (node (ref "C92") (pin "1") (pinfunction "1_1") (pintype "passive"))
      (node (ref "C96") (pin "1") (pinfunction "1_1") (pintype "passive"))
      (node (ref "C97") (pin "1") (pinfunction "1_1") (pintype "passive"))
      (node (ref "U10") (pin "43") (pinfunction "AVDD1B_43") (pintype "power_in"))
      (node (ref "U10") (pin "52") (pinfunction "AVDD2B_52") (pintype "power_in"))
      (node (ref "U10") (pin "58") (pinfunction "AVDD2A_58") (pintype "power_in"))
      (node (ref "U10") (pin "6") (pinfunction "AVDD1A_6") (pintype "power_in"))
      (node (ref "U10") (pin "62") (pinfunction "AVDD4_62") (pintype "power_in"))
      (node (ref "U3") (pin "1") (pinfunction "VOUT_1") (pintype "power_in"))
      (node (ref "U3") (pin "2") (pinfunction "S/ADJ_2") (pintype "bidirectional"))
      (node (ref "U7") (pin "43") (pinfunction "AVDD1B_43") (pintype "power_in"))
      (node (ref "U7") (pin "52") (pinfunction "AVDD2B_52") (pintype "power_in"))
      (node (ref "U7") (pin "58") (pinfunction "AVDD2A_58") (pintype "power_in"))
      (node (ref "U7") (pin "6") (pinfunction "AVDD1A_6") (pintype "power_in"))
      (node (ref "U7") (pin "62") (pinfunction "AVDD4_62") (pintype "power_in"))
      (node (ref "U8") (pin "43") (pinfunction "AVDD1B_43") (pintype "power_in"))
      (node (ref "U8") (pin "52") (pinfunction "AVDD2B_52") (pintype "power_in"))
      (node (ref "U8") (pin "58") (pinfunction "AVDD2A_58") (pintype "power_in"))
      (node (ref "U8") (pin "6") (pinfunction "AVDD1A_6") (pintype "power_in"))
      (node (ref "U8") (pin "62") (pinfunction "AVDD4_62") (pintype "power_in"))
      (node (ref "U9") (pin "43") (pinfunction "AVDD1B_43") (pintype "power_in"))
      (node (ref "U9") (pin "52") (pinfunction "AVDD2B_52") (pintype "power_in"))
      (node (ref "U9") (pin "58") (pinfunction "AVDD2A_58") (pintype "power_in"))
      (node (ref "U9") (pin "6") (pinfunction "AVDD1A_6") (pintype "power_in"))
      (node (ref "U9") (pin "62") (pinfunction "AVDD4_62") (pintype "power_in"))
    )
    (net (code "35") (name "CS") (class "Default")
      (node (ref "JP4") (pin "3") (pinfunction "3_3") (pintype "passive"))
      (node (ref "JP5") (pin "7") (pinfunction "7_7") (pintype "passive"))
      (node (ref "U10") (pin "18") (pinfunction "ALERT/CSN_18") (pintype "input"))
      (node (ref "U7") (pin "18") (pinfunction "ALERT/CSN_18") (pintype "input"))
      (node (ref "U8") (pin "18") (pinfunction "ALERT/CSN_18") (pintype "input"))
      (node (ref "U9") (pin "18") (pinfunction "ALERT/CSN_18") (pintype "input"))
    )
    (net (code "36") (name "DRDY") (class "Default")
      (node (ref "JP5") (pin "6") (pinfunction "6_6") (pintype "passive"))
      (node (ref "U8") (pin "30") (pinfunction "DRDYN_30") (pintype "output"))
    )
    (net (code "37") (name "GND") (class "Default")
      (node (ref "C1") (pin "2") (pinfunction "2_2") (pintype "passive"))
      (node (ref "C100") (pin "1") (pinfunction "1_1") (pintype "passive"))
      (node (ref "C101") (pin "1") (pinfunction "1_1") (pintype "passive"))
      (node (ref "C102") (pin "1") (pinfunction "1_1") (pintype "passive"))
      (node (ref "C11") (pin "2") (pinfunction "2_2") (pintype "passive"))
      (node (ref "C13") (pin "2") (pinfunction "2_2") (pintype "passive"))
      (node (ref "C16") (pin "2") (pinfunction "2_2") (pintype "passive"))
      (node (ref "C18") (pin "2") (pinfunction "2_2") (pintype "passive"))
      (node (ref "C19") (pin "2") (pinfunction "2_2") (pintype "passive"))
      (node (ref "C2") (pin "2") (pinfunction "2_2") (pintype "passive"))
      (node (ref "C20") (pin "2") (pinfunction "2_2") (pintype "passive"))
      (node (ref "C21") (pin "2") (pinfunction "2_2") (pintype "passive"))
      (node (ref "C22") (pin "2") (pinfunction "2_2") (pintype "passive"))
      (node (ref "C23") (pin "2") (pinfunction "2_2") (pintype "passive"))
      (node (ref "C24") (pin "2") (pinfunction "2_2") (pintype "passive"))
      (node (ref "C25") (pin "2") (pinfunction "2_2") (pintype "passive"))
      (node (ref "C26") (pin "2") (pinfunction "2_2") (pintype "passive"))
      (node (ref "C27") (pin "2") (pinfunction "2_2") (pintype "passive"))
      (node (ref "C28") (pin "2") (pinfunction "2_2") (pintype "passive"))
      (node (ref "C29") (pin "2") (pinfunction "2_2") (pintype "passive"))
      (node (ref "C3") (pin "2") (pinfunction "2_2") (pintype "passive"))
      (node (ref "C30") (pin "2") (pinfunction "2_2") (pintype "passive"))
      (node (ref "C31") (pin "2") (pinfunction "2_2") (pintype "passive"))
      (node (ref "C32") (pin "2") (pinfunction "2_2") (pintype "passive"))
      (node (ref "C33") (pin "2") (pinfunction "2_2") (pintype "passive"))
      (node (ref "C34") (pin "2") (pinfunction "2_2") (pintype "passive"))
      (node (ref "C35") (pin "2") (pinfunction "2_2") (pintype "passive"))
      (node (ref "C36") (pin "2") (pinfunction "2_2") (pintype "passive"))
      (node (ref "C37") (pin "2") (pinfunction "2_2") (pintype "passive"))
      (node (ref "C38") (pin "1") (pinfunction "1_1") (pintype "passive"))
      (node (ref "C39") (pin "2") (pinfunction "2_2") (pintype "passive"))
      (node (ref "C40") (pin "2") (pinfunction "2_2") (pintype "passive"))
      (node (ref "C41") (pin "2") (pinfunction "2_2") (pintype "passive"))
      (node (ref "C42") (pin "2") (pinfunction "2_2") (pintype "passive"))
      (node (ref "C43") (pin "1") (pinfunction "1_1") (pintype "passive"))
      (node (ref "C44") (pin "1") (pinfunction "1_1") (pintype "passive"))
      (node (ref "C45") (pin "1") (pinfunction "1_1") (pintype "passive"))
      (node (ref "C46") (pin "1") (pinfunction "1_1") (pintype "passive"))
      (node (ref "C47") (pin "2") (pinfunction "2_2") (pintype "passive"))
      (node (ref "C48") (pin "2") (pinfunction "2_2") (pintype "passive"))
      (node (ref "C49") (pin "2") (pinfunction "2_2") (pintype "passive"))
      (node (ref "C50") (pin "2") (pinfunction "2_2") (pintype "passive"))
      (node (ref "C51") (pin "2") (pinfunction "2_2") (pintype "passive"))
      (node (ref "C52") (pin "2") (pinfunction "2_2") (pintype "passive"))
      (node (ref "C53") (pin "2") (pinfunction "2_2") (pintype "passive"))
      (node (ref "C54") (pin "2") (pinfunction "2_2") (pintype "passive"))
      (node (ref "C55") (pin "2") (pinfunction "2_2") (pintype "passive"))
      (node (ref "C56") (pin "2") (pinfunction "2_2") (pintype "passive"))
      (node (ref "C57") (pin "1") (pinfunction "1_1") (pintype "passive"))
      (node (ref "C58") (pin "2") (pinfunction "2_2") (pintype "passive"))
      (node (ref "C59") (pin "2") (pinfunction "2_2") (pintype "passive"))
      (node (ref "C60") (pin "2") (pinfunction "2_2") (pintype "passive"))
      (node (ref "C61") (pin "2") (pinfunction "2_2") (pintype "passive"))
      (node (ref "C62") (pin "1") (pinfunction "1_1") (pintype "passive"))
      (node (ref "C63") (pin "2") (pinfunction "2_2") (pintype "passive"))
      (node (ref "C64") (pin "1") (pinfunction "1_1") (pintype "passive"))
      (node (ref "C65") (pin "1") (pinfunction "1_1") (pintype "passive"))
      (node (ref "C66") (pin "1") (pinfunction "1_1") (pintype "passive"))
      (node (ref "C67") (pin "2") (pinfunction "2_2") (pintype "passive"))
      (node (ref "C68") (pin "2") (pinfunction "2_2") (pintype "passive"))
      (node (ref "C69") (pin "2") (pinfunction "2_2") (pintype "passive"))
      (node (ref "C70") (pin "2") (pinfunction "2_2") (pintype "passive"))
      (node (ref "C71") (pin "2") (pinfunction "2_2") (pintype "passive"))
      (node (ref "C72") (pin "2") (pinfunction "2_2") (pintype "passive"))
      (node (ref "C73") (pin "1") (pinfunction "1_1") (pintype "passive"))
      (node (ref "C74") (pin "2") (pinfunction "2_2") (pintype "passive"))
      (node (ref "C75") (pin "2") (pinfunction "2_2") (pintype "passive"))
      (node (ref "C76") (pin "2") (pinfunction "2_2") (pintype "passive"))
      (node (ref "C77") (pin "2") (pinfunction "2_2") (pintype "passive"))
      (node (ref "C78") (pin "1") (pinfunction "1_1") (pintype "passive"))
      (node (ref "C79") (pin "2") (pinfunction "2_2") (pintype "passive"))
      (node (ref "C80") (pin "1") (pinfunction "1_1") (pintype "passive"))
      (node (ref "C81") (pin "1") (pinfunction "1_1") (pintype "passive"))
      (node (ref "C82") (pin "1") (pinfunction "1_1") (pintype "passive"))
      (node (ref "C83") (pin "2") (pinfunction "2_2") (pintype "passive"))
      (node (ref "C84") (pin "2") (pinfunction "2_2") (pintype "passive"))
      (node (ref "C85") (pin "2") (pinfunction "2_2") (pintype "passive"))
      (node (ref "C86") (pin "2") (pinfunction "2_2") (pintype "passive"))
      (node (ref "C87") (pin "2") (pinfunction "2_2") (pintype "passive"))
      (node (ref "C88") (pin "2") (pinfunction "2_2") (pintype "passive"))
      (node (ref "C89") (pin "2") (pinfunction "2_2") (pintype "passive"))
      (node (ref "C90") (pin "2") (pinfunction "2_2") (pintype "passive"))
      (node (ref "C91") (pin "2") (pinfunction "2_2") (pintype "passive"))
      (node (ref "C92") (pin "2") (pinfunction "2_2") (pintype "passive"))
      (node (ref "C93") (pin "1") (pinfunction "1_1") (pintype "passive"))
      (node (ref "C94") (pin "2") (pinfunction "2_2") (pintype "passive"))
      (node (ref "C95") (pin "2") (pinfunction "2_2") (pintype "passive"))
      (node (ref "C96") (pin "2") (pinfunction "2_2") (pintype "passive"))
      (node (ref "C97") (pin "2") (pinfunction "2_2") (pintype "passive"))
      (node (ref "C98") (pin "1") (pinfunction "1_1") (pintype "passive"))
      (node (ref "C99") (pin "2") (pinfunction "2_2") (pintype "passive"))
      (node (ref "GND_1") (pin "1") (pinfunction "1_1") (pintype "passive"))
      (node (ref "GND_1") (pin "2") (pinfunction "2_2") (pintype "passive"))
      (node (ref "JP24") (pin "1") (pinfunction "1_1") (pintype "passive"))
      (node (ref "JP24") (pin "2") (pinfunction "2_2") (pintype "passive"))
      (node (ref "U1") (pin "3") (pinfunction "GND_3") (pintype "power_in"))
      (node (ref "U1") (pin "EP") (pinfunction "EP_EP") (pintype "power_in"))
      (node (ref "U10") (pin "13") (pinfunction "MODE0/GPIO0_13") (pintype "bidirectional"))
      (node (ref "U10") (pin "14") (pinfunction "MODE1/GPIO1_14") (pintype "bidirectional"))
      (node (ref "U10") (pin "15") (pinfunction "MODE2/GPIO2_15") (pintype "bidirectional"))
      (node (ref "U10") (pin "17") (pinfunction "CONVST_SAR_17") (pintype "input"))
      (node (ref "U10") (pin "22") (pinfunction "DGND_22") (pintype "power_in"))
      (node (ref "U10") (pin "31") (pinfunction "XTAL1_31") (pintype "input"))
      (node (ref "U10") (pin "33") (pinfunction "STARTN_33") (pintype "input"))
      (node (ref "U10") (pin "42") (pinfunction "REF2-_42") (pintype "input"))
      (node (ref "U10") (pin "44") (pinfunction "AVSS1B_44") (pintype "power_in"))
      (node (ref "U10") (pin "5") (pinfunction "AVSS1A_5") (pintype "bidirectional"))
      (node (ref "U10") (pin "50") (pinfunction "AVSS2B_50") (pintype "power_in"))
      (node (ref "U10") (pin "53") (pinfunction "AVSS3_53") (pintype "power_in"))
      (node (ref "U10") (pin "56") (pinfunction "CLK_SEL_56") (pintype "input"))
      (node (ref "U10") (pin "60") (pinfunction "AVSS2A_60") (pintype "power_in"))
      (node (ref "U10") (pin "61") (pinfunction "AVSS4_61") (pintype "power_in"))
      (node (ref "U10") (pin "65") (pinfunction "EPAD_65") (pintype "power_in"))
      (node (ref "U10") (pin "7") (pinfunction "REF1-_7") (pintype "bidirectional"))
      (node (ref "U3") (pin "3") (pinfunction "GND_3") (pintype "power_in"))
      (node (ref "U3") (pin "EP") (pinfunction "EP_EP") (pintype "power_in"))
      (node (ref "U6") (pin "4") (pinfunction "GND_4") (pintype "passive"))
      (node (ref "U7") (pin "13") (pinfunction "MODE0/GPIO0_13") (pintype "bidirectional"))
      (node (ref "U7") (pin "14") (pinfunction "MODE1/GPIO1_14") (pintype "bidirectional"))
      (node (ref "U7") (pin "15") (pinfunction "MODE2/GPIO2_15") (pintype "bidirectional"))
      (node (ref "U7") (pin "17") (pinfunction "CONVST_SAR_17") (pintype "input"))
      (node (ref "U7") (pin "22") (pinfunction "DGND_22") (pintype "power_in"))
      (node (ref "U7") (pin "31") (pinfunction "XTAL1_31") (pintype "input"))
      (node (ref "U7") (pin "33") (pinfunction "STARTN_33") (pintype "input"))
      (node (ref "U7") (pin "42") (pinfunction "REF2-_42") (pintype "input"))
      (node (ref "U7") (pin "44") (pinfunction "AVSS1B_44") (pintype "power_in"))
      (node (ref "U7") (pin "5") (pinfunction "AVSS1A_5") (pintype "bidirectional"))
      (node (ref "U7") (pin "50") (pinfunction "AVSS2B_50") (pintype "power_in"))
      (node (ref "U7") (pin "53") (pinfunction "AVSS3_53") (pintype "power_in"))
      (node (ref "U7") (pin "56") (pinfunction "CLK_SEL_56") (pintype "input"))
      (node (ref "U7") (pin "60") (pinfunction "AVSS2A_60") (pintype "power_in"))
      (node (ref "U7") (pin "61") (pinfunction "AVSS4_61") (pintype "power_in"))
      (node (ref "U7") (pin "65") (pinfunction "EPAD_65") (pintype "power_in"))
      (node (ref "U7") (pin "7") (pinfunction "REF1-_7") (pintype "bidirectional"))
      (node (ref "U8") (pin "13") (pinfunction "MODE0/GPIO0_13") (pintype "bidirectional"))
      (node (ref "U8") (pin "14") (pinfunction "MODE1/GPIO1_14") (pintype "bidirectional"))
      (node (ref "U8") (pin "15") (pinfunction "MODE2/GPIO2_15") (pintype "bidirectional"))
      (node (ref "U8") (pin "17") (pinfunction "CONVST_SAR_17") (pintype "input"))
      (node (ref "U8") (pin "22") (pinfunction "DGND_22") (pintype "power_in"))
      (node (ref "U8") (pin "31") (pinfunction "XTAL1_31") (pintype "input"))
      (node (ref "U8") (pin "33") (pinfunction "STARTN_33") (pintype "input"))
      (node (ref "U8") (pin "42") (pinfunction "REF2-_42") (pintype "input"))
      (node (ref "U8") (pin "44") (pinfunction "AVSS1B_44") (pintype "power_in"))
      (node (ref "U8") (pin "5") (pinfunction "AVSS1A_5") (pintype "bidirectional"))
      (node (ref "U8") (pin "50") (pinfunction "AVSS2B_50") (pintype "power_in"))
      (node (ref "U8") (pin "53") (pinfunction "AVSS3_53") (pintype "power_in"))
      (node (ref "U8") (pin "56") (pinfunction "CLK_SEL_56") (pintype "input"))
      (node (ref "U8") (pin "60") (pinfunction "AVSS2A_60") (pintype "power_in"))
      (node (ref "U8") (pin "61") (pinfunction "AVSS4_61") (pintype "power_in"))
      (node (ref "U8") (pin "65") (pinfunction "EPAD_65") (pintype "power_in"))
      (node (ref "U8") (pin "7") (pinfunction "REF1-_7") (pintype "bidirectional"))
      (node (ref "U9") (pin "13") (pinfunction "MODE0/GPIO0_13") (pintype "bidirectional"))
      (node (ref "U9") (pin "14") (pinfunction "MODE1/GPIO1_14") (pintype "bidirectional"))
      (node (ref "U9") (pin "15") (pinfunction "MODE2/GPIO2_15") (pintype "bidirectional"))
      (node (ref "U9") (pin "17") (pinfunction "CONVST_SAR_17") (pintype "input"))
      (node (ref "U9") (pin "22") (pinfunction "DGND_22") (pintype "power_in"))
      (node (ref "U9") (pin "31") (pinfunction "XTAL1_31") (pintype "input"))
      (node (ref "U9") (pin "42") (pinfunction "REF2-_42") (pintype "input"))
      (node (ref "U9") (pin "44") (pinfunction "AVSS1B_44") (pintype "power_in"))
      (node (ref "U9") (pin "5") (pinfunction "AVSS1A_5") (pintype "bidirectional"))
      (node (ref "U9") (pin "50") (pinfunction "AVSS2B_50") (pintype "power_in"))
      (node (ref "U9") (pin "53") (pinfunction "AVSS3_53") (pintype "power_in"))
      (node (ref "U9") (pin "56") (pinfunction "CLK_SEL_56") (pintype "input"))
      (node (ref "U9") (pin "60") (pinfunction "AVSS2A_60") (pintype "power_in"))
      (node (ref "U9") (pin "61") (pinfunction "AVSS4_61") (pintype "power_in"))
      (node (ref "U9") (pin "65") (pinfunction "EPAD_65") (pintype "power_in"))
      (node (ref "U9") (pin "7") (pinfunction "REF1-_7") (pintype "bidirectional"))
      (node (ref "Y1") (pin "P$2") (pinfunction "GND_P$2") (pintype "passive"))
    )
    (net (code "38") (name "IOVDD") (class "Default")
      (node (ref "C2") (pin "1") (pinfunction "1_1") (pintype "passive"))
      (node (ref "C26") (pin "1") (pinfunction "1_1") (pintype "passive"))
      (node (ref "C39") (pin "1") (pinfunction "1_1") (pintype "passive"))
      (node (ref "C40") (pin "1") (pinfunction "1_1") (pintype "passive"))
      (node (ref "C58") (pin "1") (pinfunction "1_1") (pintype "passive"))
      (node (ref "C59") (pin "1") (pinfunction "1_1") (pintype "passive"))
      (node (ref "C74") (pin "1") (pinfunction "1_1") (pintype "passive"))
      (node (ref "C75") (pin "1") (pinfunction "1_1") (pintype "passive"))
      (node (ref "C94") (pin "1") (pinfunction "1_1") (pintype "passive"))
      (node (ref "C95") (pin "1") (pinfunction "1_1") (pintype "passive"))
      (node (ref "IOVDD") (pin "1") (pinfunction "1_1") (pintype "passive"))
      (node (ref "JP24") (pin "3") (pinfunction "3_3") (pintype "passive"))
      (node (ref "JP24") (pin "4") (pinfunction "4_4") (pintype "passive"))
      (node (ref "R14") (pin "2") (pinfunction "2_2") (pintype "passive"))
      (node (ref "R23") (pin "2") (pinfunction "2_2") (pintype "passive"))
      (node (ref "R24") (pin "2") (pinfunction "2_2") (pintype "passive"))
      (node (ref "R6") (pin "2") (pinfunction "2_2") (pintype "passive"))
      (node (ref "U1") (pin "1") (pinfunction "VOUT_1") (pintype "power_in"))
      (node (ref "U1") (pin "2") (pinfunction "S/ADJ_2") (pintype "bidirectional"))
      (node (ref "U10") (pin "24") (pinfunction "IOVDD_24") (pintype "power_in"))
      (node (ref "U10") (pin "54") (pinfunction "FORMAT1_54") (pintype "input"))
      (node (ref "U10") (pin "55") (pinfunction "FORMAT0_55") (pintype "input"))
      (node (ref "U7") (pin "24") (pinfunction "IOVDD_24") (pintype "power_in"))
      (node (ref "U7") (pin "54") (pinfunction "FORMAT1_54") (pintype "input"))
      (node (ref "U7") (pin "55") (pinfunction "FORMAT0_55") (pintype "input"))
      (node (ref "U8") (pin "24") (pinfunction "IOVDD_24") (pintype "power_in"))
      (node (ref "U8") (pin "54") (pinfunction "FORMAT1_54") (pintype "input"))
      (node (ref "U8") (pin "55") (pinfunction "FORMAT0_55") (pintype "input"))
      (node (ref "U9") (pin "24") (pinfunction "IOVDD_24") (pintype "power_in"))
      (node (ref "U9") (pin "54") (pinfunction "FORMAT1_54") (pintype "input"))
      (node (ref "U9") (pin "55") (pinfunction "FORMAT0_55") (pintype "input"))
      (node (ref "Y1") (pin "P$1") (pinfunction "TRI_P$1") (pintype "bidirectional"))
      (node (ref "Y1") (pin "P$4") (pinfunction "VDD_P$4") (pintype "power_in"))
    )
    (net (code "39") (name "Net-(U1-SS)") (class "Default")
      (node (ref "C3") (pin "1") (pinfunction "1_1") (pintype "passive"))
      (node (ref "U1") (pin "5") (pinfunction "SS_5") (pintype "bidirectional"))
    )
    (net (code "40") (name "Net-(U3-SS)") (class "Default")
      (node (ref "C67") (pin "1") (pinfunction "1_1") (pintype "passive"))
      (node (ref "U3") (pin "5") (pinfunction "SS_5") (pintype "bidirectional"))
    )
    (net (code "41") (name "Net-(U6-VOUT)") (class "Default")
      (node (ref "R15") (pin "1") (pinfunction "1_1") (pintype "passive"))
      (node (ref "U6") (pin "6") (pinfunction "VOUT_6") (pintype "output"))
    )
    (net (code "42") (name "Net-(U7-AREG1CAP)") (class "Default")
      (node (ref "C78") (pin "2") (pinfunction "2_2") (pintype "passive"))
      (node (ref "U7") (pin "59") (pinfunction "AREG1CAP_59") (pintype "power_in"))
    )
    (net (code "43") (name "Net-(U7-AREG2CAP)") (class "Default")
      (node (ref "C79") (pin "1") (pinfunction "1_1") (pintype "passive"))
      (node (ref "U7") (pin "51") (pinfunction "AREG2CAP_51") (pintype "power_in"))
    )
    (net (code "44") (name "Net-(U7-DREGCAP)") (class "Default")
      (node (ref "C73") (pin "2") (pinfunction "2_2") (pintype "passive"))
      (node (ref "U7") (pin "23") (pinfunction "DREGCAP_23") (pintype "power_in"))
    )
    (net (code "45") (name "Net-(U7-REF_OUT)") (class "Default")
      (node (ref "C82") (pin "2") (pinfunction "2_2") (pintype "passive"))
      (node (ref "U7") (pin "49") (pinfunction "REF_OUT_49") (pintype "output"))
    )
    (net (code "46") (name "Net-(U8-AREG1CAP)") (class "Default")
      (node (ref "C43") (pin "2") (pinfunction "2_2") (pintype "passive"))
      (node (ref "U8") (pin "59") (pinfunction "AREG1CAP_59") (pintype "power_in"))
    )
    (net (code "47") (name "Net-(U8-AREG2CAP)") (class "Default")
      (node (ref "C42") (pin "1") (pinfunction "1_1") (pintype "passive"))
      (node (ref "U8") (pin "51") (pinfunction "AREG2CAP_51") (pintype "power_in"))
    )
    (net (code "48") (name "Net-(U8-DREGCAP)") (class "Default")
      (node (ref "C38") (pin "2") (pinfunction "2_2") (pintype "passive"))
      (node (ref "U8") (pin "23") (pinfunction "DREGCAP_23") (pintype "power_in"))
    )
    (net (code "49") (name "Net-(U8-REF_OUT)") (class "Default")
      (node (ref "C46") (pin "2") (pinfunction "2_2") (pintype "passive"))
      (node (ref "U8") (pin "49") (pinfunction "REF_OUT_49") (pintype "output"))
    )
    (net (code "50") (name "Net-(U9-AREG1CAP)") (class "Default")
      (node (ref "C62") (pin "2") (pinfunction "2_2") (pintype "passive"))
      (node (ref "U9") (pin "59") (pinfunction "AREG1CAP_59") (pintype "power_in"))
    )
    (net (code "51") (name "Net-(U9-AREG2CAP)") (class "Default")
      (node (ref "C63") (pin "1") (pinfunction "1_1") (pintype "passive"))
      (node (ref "U9") (pin "51") (pinfunction "AREG2CAP_51") (pintype "power_in"))
    )
    (net (code "52") (name "Net-(U9-DREGCAP)") (class "Default")
      (node (ref "C57") (pin "2") (pinfunction "2_2") (pintype "passive"))
      (node (ref "U9") (pin "23") (pinfunction "DREGCAP_23") (pintype "power_in"))
    )
    (net (code "53") (name "Net-(U9-REF_OUT)") (class "Default")
      (node (ref "C66") (pin "2") (pinfunction "2_2") (pintype "passive"))
      (node (ref "U9") (pin "49") (pinfunction "REF_OUT_49") (pintype "output"))
    )
    (net (code "54") (name "Net-(U10-AREG1CAP)") (class "Default")
      (node (ref "C98") (pin "2") (pinfunction "2_2") (pintype "passive"))
      (node (ref "U10") (pin "59") (pinfunction "AREG1CAP_59") (pintype "power_in"))
    )
    (net (code "55") (name "Net-(U10-AREG2CAP)") (class "Default")
      (node (ref "C99") (pin "1") (pinfunction "1_1") (pintype "passive"))
      (node (ref "U10") (pin "51") (pinfunction "AREG2CAP_51") (pintype "power_in"))
    )
    (net (code "56") (name "Net-(U10-DREGCAP)") (class "Default")
      (node (ref "C93") (pin "2") (pinfunction "2_2") (pintype "passive"))
      (node (ref "U10") (pin "23") (pinfunction "DREGCAP_23") (pintype "power_in"))
    )
    (net (code "57") (name "Net-(U10-REF_OUT)") (class "Default")
      (node (ref "C102") (pin "2") (pinfunction "2_2") (pintype "passive"))
      (node (ref "U10") (pin "49") (pinfunction "REF_OUT_49") (pintype "output"))
    )
    (net (code "58") (name "RESET") (class "Default")
      (node (ref "JP4") (pin "2") (pinfunction "2_2") (pintype "passive"))
      (node (ref "JP5") (pin "8") (pinfunction "8_8") (pintype "passive"))
      (node (ref "R14") (pin "1") (pinfunction "1_1") (pintype "passive"))
      (node (ref "R23") (pin "1") (pinfunction "1_1") (pintype "passive"))
      (node (ref "R24") (pin "1") (pinfunction "1_1") (pintype "passive"))
      (node (ref "R6") (pin "1") (pinfunction "1_1") (pintype "passive"))
      (node (ref "U10") (pin "36") (pinfunction "RESETN_36") (pintype "input"))
      (node (ref "U7") (pin "36") (pinfunction "RESETN_36") (pintype "input"))
      (node (ref "U8") (pin "36") (pinfunction "RESETN_36") (pintype "input"))
      (node (ref "U9") (pin "36") (pinfunction "RESETN_36") (pintype "input"))
    )
    (net (code "59") (name "SCLK") (class "Default")
      (node (ref "JP4") (pin "4") (pinfunction "4_4") (pintype "passive"))
      (node (ref "JP5") (pin "5") (pinfunction "5_5") (pintype "passive"))
      (node (ref "U10") (pin "19") (pinfunction "DCLK2/SCLK_19") (pintype "input"))
      (node (ref "U7") (pin "19") (pinfunction "DCLK2/SCLK_19") (pintype "input"))
      (node (ref "U8") (pin "19") (pinfunction "DCLK2/SCLK_19") (pintype "input"))
      (node (ref "U9") (pin "19") (pinfunction "DCLK2/SCLK_19") (pintype "input"))
    )
    (net (code "60") (name "SDI") (class "Default")
      (node (ref "JP4") (pin "1") (pinfunction "1_1") (pintype "passive"))
      (node (ref "JP5") (pin "3") (pinfunction "3_3") (pintype "passive"))
      (node (ref "U10") (pin "20") (pinfunction "DCLK1/SDI_20") (pintype "input"))
      (node (ref "U7") (pin "20") (pinfunction "DCLK1/SDI_20") (pintype "input"))
      (node (ref "U8") (pin "20") (pinfunction "DCLK1/SDI_20") (pintype "input"))
      (node (ref "U9") (pin "20") (pinfunction "DCLK1/SDI_20") (pintype "input"))
    )
    (net (code "61") (name "SDO_0") (class "Default")
      (node (ref "JP5") (pin "4") (pinfunction "4_4") (pintype "passive"))
      (node (ref "U8") (pin "21") (pinfunction "DCLK0/SDO_21") (pintype "output"))
    )
    (net (code "62") (name "SDO_1") (class "Default")
      (node (ref "JP5") (pin "1") (pinfunction "1_1") (pintype "passive"))
      (node (ref "U9") (pin "21") (pinfunction "DCLK0/SDO_21") (pintype "output"))
    )
    (net (code "63") (name "SDO_2") (class "Default")
      (node (ref "JP4") (pin "5") (pinfunction "5_5") (pintype "passive"))
      (node (ref "U7") (pin "21") (pinfunction "DCLK0/SDO_21") (pintype "output"))
    )
    (net (code "64") (name "SDO_3") (class "Default")
      (node (ref "JP4") (pin "6") (pinfunction "6_6") (pintype "passive"))
      (node (ref "U10") (pin "21") (pinfunction "DCLK0/SDO_21") (pintype "output"))
    )
    (net (code "65") (name "STARTN") (class "Default")
      (node (ref "JP5") (pin "2") (pinfunction "2_2") (pintype "passive"))
      (node (ref "U9") (pin "33") (pinfunction "STARTN_33") (pintype "input"))
    )
    (net (code "66") (name "SYNC_FROM_ADC") (class "Default")
      (node (ref "U10") (pin "35") (pinfunction "SYNC_INN_35") (pintype "input"))
      (node (ref "U7") (pin "35") (pinfunction "SYNC_INN_35") (pintype "input"))
      (node (ref "U8") (pin "35") (pinfunction "SYNC_INN_35") (pintype "input"))
      (node (ref "U9") (pin "34") (pinfunction "SYNC_OUTN_34") (pintype "input"))
      (node (ref "U9") (pin "35") (pinfunction "SYNC_INN_35") (pintype "input"))
    )
    (net (code "67") (name "VCM_ADC1") (class "Default")
      (node (ref "JP_VCM_OUT") (pin "1") (pinfunction "1_1") (pintype "passive"))
      (node (ref "U8") (pin "57") (pinfunction "VCM_57") (pintype "output"))
    )
    (net (code "68") (name "VPOS") (class "Default")
      (node (ref "C1") (pin "1") (pinfunction "1_1") (pintype "passive"))
      (node (ref "C13") (pin "1") (pinfunction "1_1") (pintype "passive"))
      (node (ref "C16") (pin "1") (pinfunction "1_1") (pintype "passive"))
      (node (ref "C25") (pin "1") (pinfunction "1_1") (pintype "passive"))
      (node (ref "JP_VPOS1") (pin "1") (pinfunction "1_1") (pintype "passive"))
      (node (ref "JP_VPOS1") (pin "2") (pinfunction "2_2") (pintype "passive"))
      (node (ref "U1") (pin "4") (pinfunction "EN_4") (pintype "bidirectional"))
      (node (ref "U1") (pin "6") (pinfunction "VIN_6") (pintype "power_in"))
      (node (ref "U3") (pin "4") (pinfunction "EN_4") (pintype "bidirectional"))
      (node (ref "U3") (pin "6") (pinfunction "VIN_6") (pintype "power_in"))
      (node (ref "U6") (pin "2") (pinfunction "VIN_2") (pintype "input"))
    )
    (net (code "69") (name "VREF") (class "Default")
      (node (ref "C11") (pin "1") (pinfunction "1_1") (pintype "passive"))
      (node (ref "C18") (pin "1") (pinfunction "1_1") (pintype "passive"))
      (node (ref "C19") (pin "1") (pinfunction "1_1") (pintype "passive"))
      (node (ref "C20") (pin "1") (pinfunction "1_1") (pintype "passive"))
      (node (ref "C21") (pin "1") (pinfunction "1_1") (pintype "passive"))
      (node (ref "C22") (pin "1") (pinfunction "1_1") (pintype "passive"))
      (node (ref "C27") (pin "1") (pinfunction "1_1") (pintype "passive"))
      (node (ref "C28") (pin "1") (pinfunction "1_1") (pintype "passive"))
      (node (ref "C29") (pin "1") (pinfunction "1_1") (pintype "passive"))
      (node (ref "C30") (pin "1") (pinfunction "1_1") (pintype "passive"))
      (node (ref "C47") (pin "1") (pinfunction "1_1") (pintype "passive"))
      (node (ref "C48") (pin "1") (pinfunction "1_1") (pintype "passive"))
      (node (ref "C49") (pin "1") (pinfunction "1_1") (pintype "passive"))
      (node (ref "C50") (pin "1") (pinfunction "1_1") (pintype "passive"))
      (node (ref "C83") (pin "1") (pinfunction "1_1") (pintype "passive"))
      (node (ref "C84") (pin "1") (pinfunction "1_1") (pintype "passive"))
      (node (ref "C85") (pin "1") (pinfunction "1_1") (pintype "passive"))
      (node (ref "C86") (pin "1") (pinfunction "1_1") (pintype "passive"))
      (node (ref "R15") (pin "2") (pinfunction "2_2") (pintype "passive"))
      (node (ref "U10") (pin "41") (pinfunction "REF2+_41") (pintype "input"))
      (node (ref "U10") (pin "8") (pinfunction "REF1+_8") (pintype "input"))
      (node (ref "U7") (pin "41") (pinfunction "REF2+_41") (pintype "input"))
      (node (ref "U7") (pin "8") (pinfunction "REF1+_8") (pintype "input"))
      (node (ref "U8") (pin "41") (pinfunction "REF2+_41") (pintype "input"))
      (node (ref "U8") (pin "8") (pinfunction "REF1+_8") (pintype "input"))
      (node (ref "U9") (pin "41") (pinfunction "REF2+_41") (pintype "input"))
      (node (ref "U9") (pin "8") (pinfunction "REF1+_8") (pintype "input"))
      (node (ref "VREF") (pin "1") (pinfunction "1_1") (pintype "passive"))
    )
    (net (code "70") (name "XTAL_OUT") (class "Default")
      (node (ref "U10") (pin "32") (pinfunction "XTAL2/MCLK_32") (pintype "input"))
      (node (ref "U7") (pin "32") (pinfunction "XTAL2/MCLK_32") (pintype "input"))
      (node (ref "U8") (pin "32") (pinfunction "XTAL2/MCLK_32") (pintype "input"))
      (node (ref "U9") (pin "32") (pinfunction "XTAL2/MCLK_32") (pintype "input"))
      (node (ref "Y1") (pin "P$3") (pinfunction "OUT_P$3") (pintype "output"))
    )
    (net (code "71") (name "unconnected-(U6-DNC1-Pad1)") (class "Default")
      (node (ref "U6") (pin "1") (pinfunction "DNC1_1") (pintype "no_connect"))
    )
    (net (code "72") (name "unconnected-(U6-DNC2-Pad8)") (class "Default")
      (node (ref "U6") (pin "8") (pinfunction "DNC2_8") (pintype "no_connect"))
    )
    (net (code "73") (name "unconnected-(U6-NIC1-Pad3)") (class "Default")
      (node (ref "U6") (pin "3") (pinfunction "NIC1_3") (pintype "no_connect"))
    )
    (net (code "74") (name "unconnected-(U6-NIC2-Pad7)") (class "Default")
      (node (ref "U6") (pin "7") (pinfunction "NIC2_7") (pintype "no_connect"))
    )
    (net (code "75") (name "unconnected-(U6-TRIM-Pad5)") (class "Default")
      (node (ref "U6") (pin "5") (pinfunction "TRIM_5") (pintype "input"))
    )
    (net (code "76") (name "unconnected-(U7-AUXAIN+-Pad63)") (class "Default")
      (node (ref "U7") (pin "63") (pinfunction "AUXAIN+_63") (pintype "input"))
    )
    (net (code "77") (name "unconnected-(U7-AUXAIN--Pad64)") (class "Default")
      (node (ref "U7") (pin "64") (pinfunction "AUXAIN-_64") (pintype "input"))
    )
    (net (code "78") (name "unconnected-(U7-DCLK-Pad29)") (class "Default")
      (node (ref "U7") (pin "29") (pinfunction "DCLK_29") (pintype "output"))
    )
    (net (code "79") (name "unconnected-(U7-DOUT0-Pad28)") (class "Default")
      (node (ref "U7") (pin "28") (pinfunction "DOUT0_28") (pintype "output"))
    )
    (net (code "80") (name "unconnected-(U7-DOUT1-Pad27)") (class "Default")
      (node (ref "U7") (pin "27") (pinfunction "DOUT1_27") (pintype "output"))
    )
    (net (code "81") (name "unconnected-(U7-DOUT2-Pad26)") (class "Default")
      (node (ref "U7") (pin "26") (pinfunction "DOUT2_26") (pintype "bidirectional"))
    )
    (net (code "82") (name "unconnected-(U7-DOUT3-Pad25)") (class "Default")
      (node (ref "U7") (pin "25") (pinfunction "DOUT3_25") (pintype "bidirectional"))
    )
    (net (code "83") (name "unconnected-(U7-DRDYN-Pad30)") (class "Default")
      (node (ref "U7") (pin "30") (pinfunction "DRDYN_30") (pintype "output"))
    )
    (net (code "84") (name "unconnected-(U7-MODE3{slash}ALERT-Pad16)") (class "Default")
      (node (ref "U7") (pin "16") (pinfunction "MODE3/ALERT_16") (pintype "bidirectional"))
    )
    (net (code "85") (name "unconnected-(U7-SYNC_OUTN-Pad34)") (class "Default")
      (node (ref "U7") (pin "34") (pinfunction "SYNC_OUTN_34") (pintype "input"))
    )
    (net (code "86") (name "unconnected-(U7-VCM-Pad57)") (class "Default")
      (node (ref "U7") (pin "57") (pinfunction "VCM_57") (pintype "output"))
    )
    (net (code "87") (name "unconnected-(U8-AUXAIN+-Pad63)") (class "Default")
      (node (ref "U8") (pin "63") (pinfunction "AUXAIN+_63") (pintype "input"))
    )
    (net (code "88") (name "unconnected-(U8-AUXAIN--Pad64)") (class "Default")
      (node (ref "U8") (pin "64") (pinfunction "AUXAIN-_64") (pintype "input"))
    )
    (net (code "89") (name "unconnected-(U8-DCLK-Pad29)") (class "Default")
      (node (ref "U8") (pin "29") (pinfunction "DCLK_29") (pintype "output"))
    )
    (net (code "90") (name "unconnected-(U8-DOUT0-Pad28)") (class "Default")
      (node (ref "U8") (pin "28") (pinfunction "DOUT0_28") (pintype "output"))
    )
    (net (code "91") (name "unconnected-(U8-DOUT1-Pad27)") (class "Default")
      (node (ref "U8") (pin "27") (pinfunction "DOUT1_27") (pintype "output"))
    )
    (net (code "92") (name "unconnected-(U8-DOUT2-Pad26)") (class "Default")
      (node (ref "U8") (pin "26") (pinfunction "DOUT2_26") (pintype "bidirectional"))
    )
    (net (code "93") (name "unconnected-(U8-DOUT3-Pad25)") (class "Default")
      (node (ref "U8") (pin "25") (pinfunction "DOUT3_25") (pintype "bidirectional"))
    )
    (net (code "94") (name "unconnected-(U8-MODE3{slash}ALERT-Pad16)") (class "Default")
      (node (ref "U8") (pin "16") (pinfunction "MODE3/ALERT_16") (pintype "bidirectional"))
    )
    (net (code "95") (name "unconnected-(U8-SYNC_OUTN-Pad34)") (class "Default")
      (node (ref "U8") (pin "34") (pinfunction "SYNC_OUTN_34") (pintype "input"))
    )
    (net (code "96") (name "unconnected-(U9-AUXAIN+-Pad63)") (class "Default")
      (node (ref "U9") (pin "63") (pinfunction "AUXAIN+_63") (pintype "input"))
    )
    (net (code "97") (name "unconnected-(U9-AUXAIN--Pad64)") (class "Default")
      (node (ref "U9") (pin "64") (pinfunction "AUXAIN-_64") (pintype "input"))
    )
    (net (code "98") (name "unconnected-(U9-DCLK-Pad29)") (class "Default")
      (node (ref "U9") (pin "29") (pinfunction "DCLK_29") (pintype "output"))
    )
    (net (code "99") (name "unconnected-(U9-DOUT0-Pad28)") (class "Default")
      (node (ref "U9") (pin "28") (pinfunction "DOUT0_28") (pintype "output"))
    )
    (net (code "100") (name "unconnected-(U9-DOUT1-Pad27)") (class "Default")
      (node (ref "U9") (pin "27") (pinfunction "DOUT1_27") (pintype "output"))
    )
    (net (code "101") (name "unconnected-(U9-DOUT2-Pad26)") (class "Default")
      (node (ref "U9") (pin "26") (pinfunction "DOUT2_26") (pintype "bidirectional"))
    )
    (net (code "102") (name "unconnected-(U9-DOUT3-Pad25)") (class "Default")
      (node (ref "U9") (pin "25") (pinfunction "DOUT3_25") (pintype "bidirectional"))
    )
    (net (code "103") (name "unconnected-(U9-DRDYN-Pad30)") (class "Default")
      (node (ref "U9") (pin "30") (pinfunction "DRDYN_30") (pintype "output"))
    )
    (net (code "104") (name "unconnected-(U9-MODE3{slash}ALERT-Pad16)") (class "Default")
      (node (ref "U9") (pin "16") (pinfunction "MODE3/ALERT_16") (pintype "bidirectional"))
    )
    (net (code "105") (name "unconnected-(U9-VCM-Pad57)") (class "Default")
      (node (ref "U9") (pin "57") (pinfunction "VCM_57") (pintype "output"))
    )
    (net (code "106") (name "unconnected-(U10-AUXAIN+-Pad63)") (class "Default")
      (node (ref "U10") (pin "63") (pinfunction "AUXAIN+_63") (pintype "input"))
    )
    (net (code "107") (name "unconnected-(U10-AUXAIN--Pad64)") (class "Default")
      (node (ref "U10") (pin "64") (pinfunction "AUXAIN-_64") (pintype "input"))
    )
    (net (code "108") (name "unconnected-(U10-DCLK-Pad29)") (class "Default")
      (node (ref "U10") (pin "29") (pinfunction "DCLK_29") (pintype "output"))
    )
    (net (code "109") (name "unconnected-(U10-DOUT0-Pad28)") (class "Default")
      (node (ref "U10") (pin "28") (pinfunction "DOUT0_28") (pintype "output"))
    )
    (net (code "110") (name "unconnected-(U10-DOUT1-Pad27)") (class "Default")
      (node (ref "U10") (pin "27") (pinfunction "DOUT1_27") (pintype "output"))
    )
    (net (code "111") (name "unconnected-(U10-DOUT2-Pad26)") (class "Default")
      (node (ref "U10") (pin "26") (pinfunction "DOUT2_26") (pintype "bidirectional"))
    )
    (net (code "112") (name "unconnected-(U10-DOUT3-Pad25)") (class "Default")
      (node (ref "U10") (pin "25") (pinfunction "DOUT3_25") (pintype "bidirectional"))
    )
    (net (code "113") (name "unconnected-(U10-DRDYN-Pad30)") (class "Default")
      (node (ref "U10") (pin "30") (pinfunction "DRDYN_30") (pintype "output"))
    )
    (net (code "114") (name "unconnected-(U10-MODE3{slash}ALERT-Pad16)") (class "Default")
      (node (ref "U10") (pin "16") (pinfunction "MODE3/ALERT_16") (pintype "bidirectional"))
    )
    (net (code "115") (name "unconnected-(U10-SYNC_OUTN-Pad34)") (class "Default")
      (node (ref "U10") (pin "34") (pinfunction "SYNC_OUTN_34") (pintype "input"))
    )
    (net (code "116") (name "unconnected-(U10-VCM-Pad57)") (class "Default")
      (node (ref "U10") (pin "57") (pinfunction "VCM_57") (pintype "output"))
    )
  )
)
